# Modulator_and_Front_End.net
KiCad netlist of a schematic drawn in EAGLE
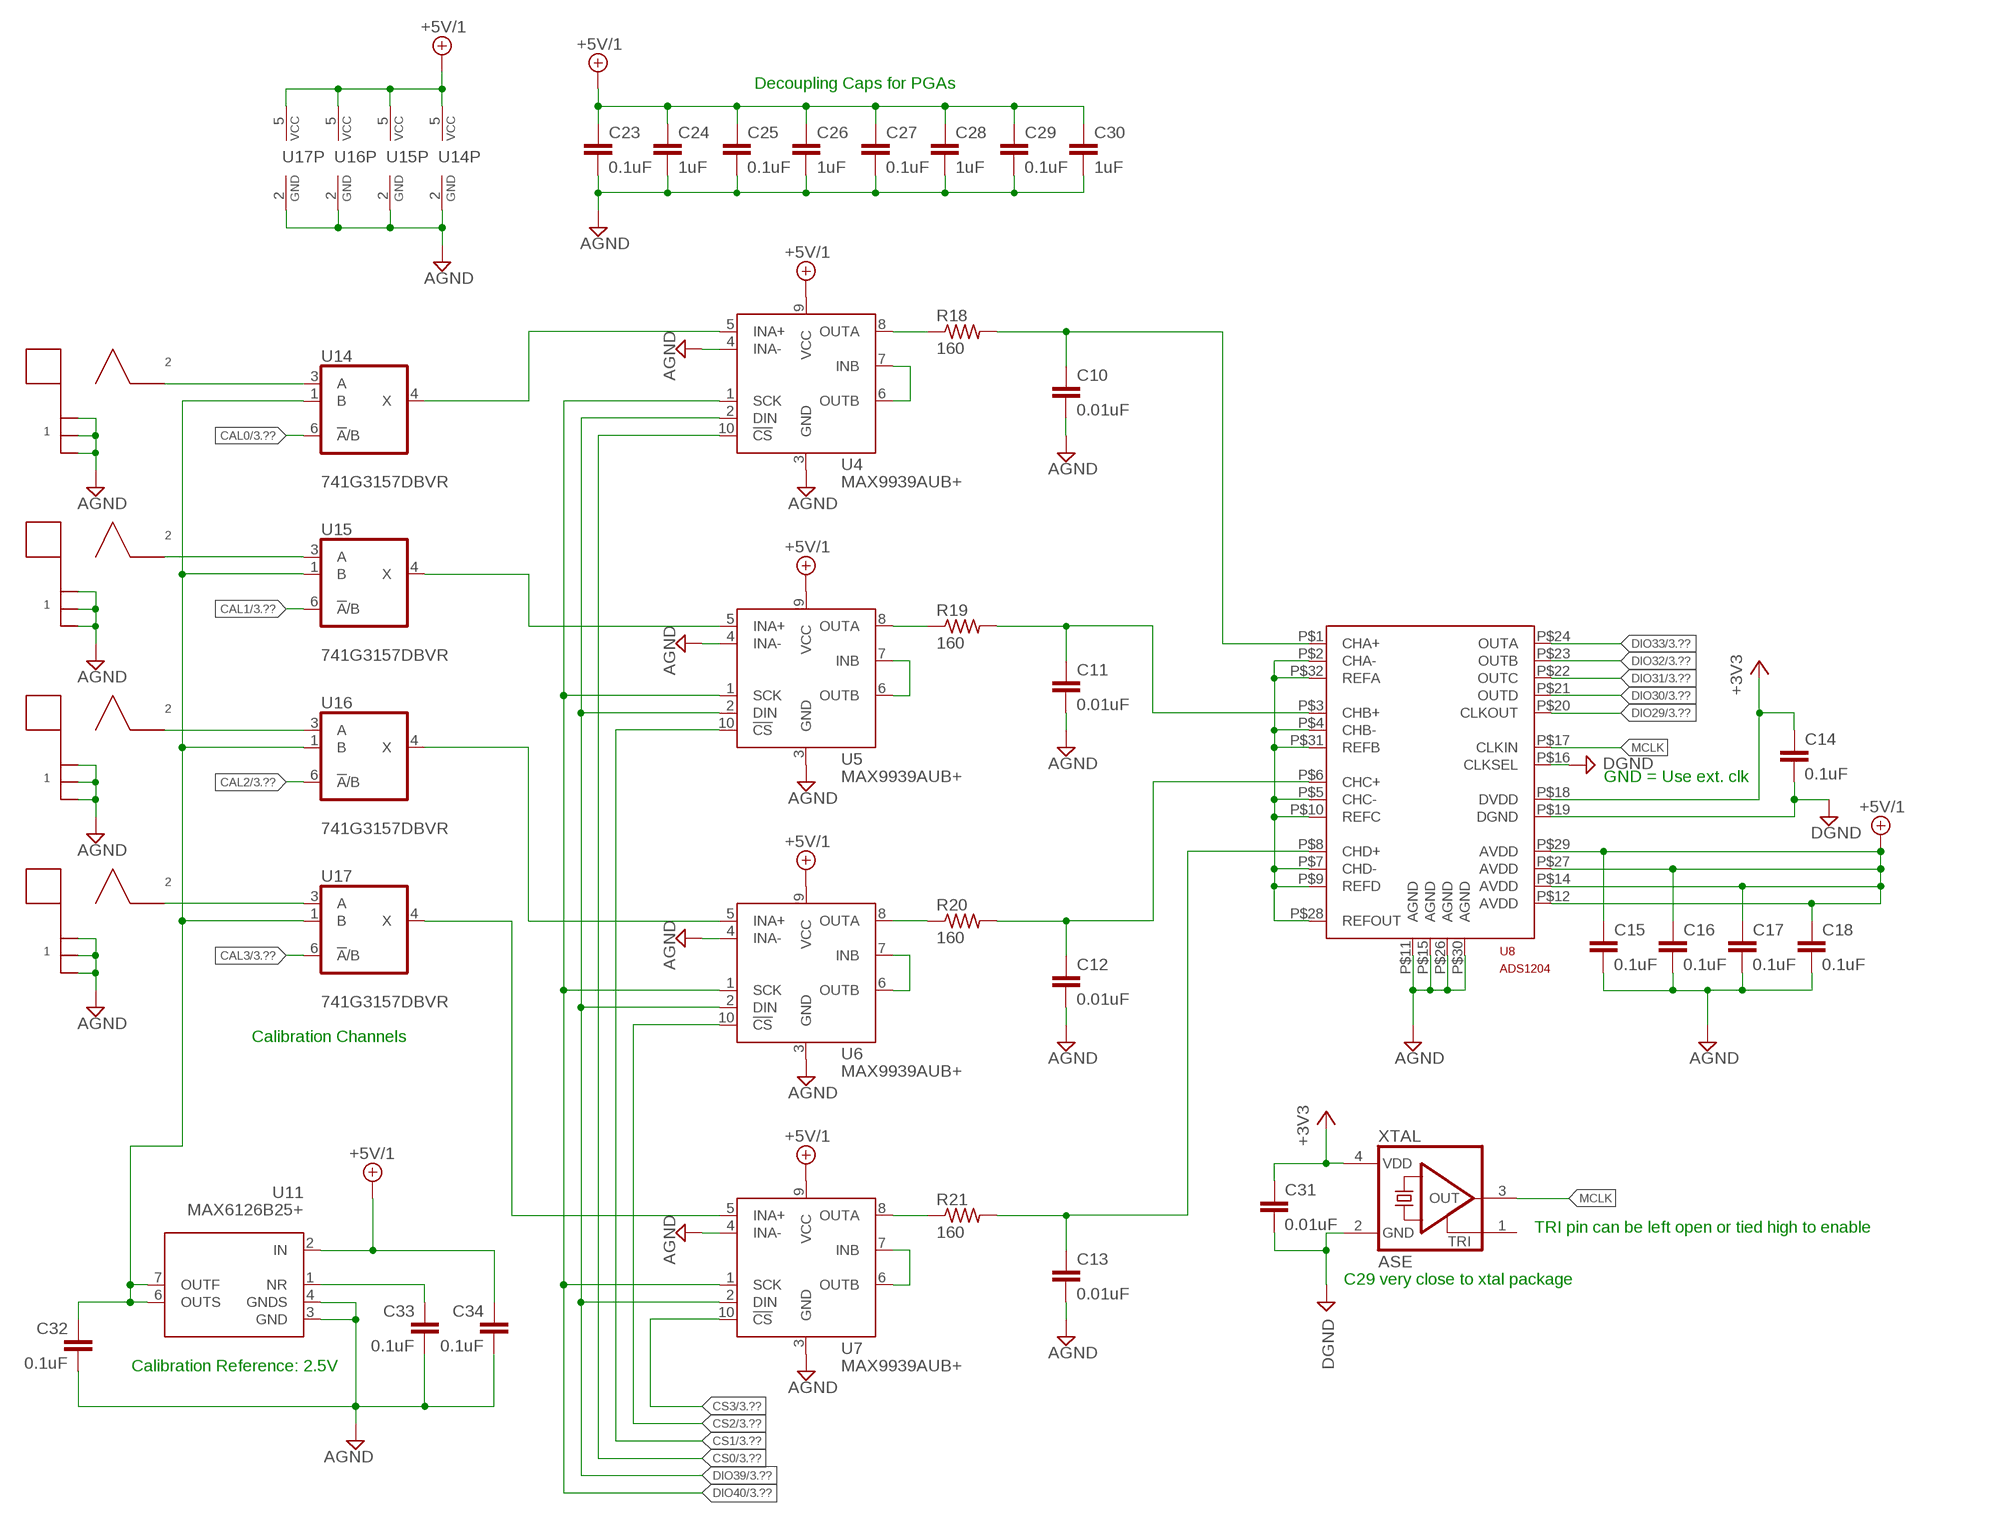
[diagram p0: schematic, sheet 1]
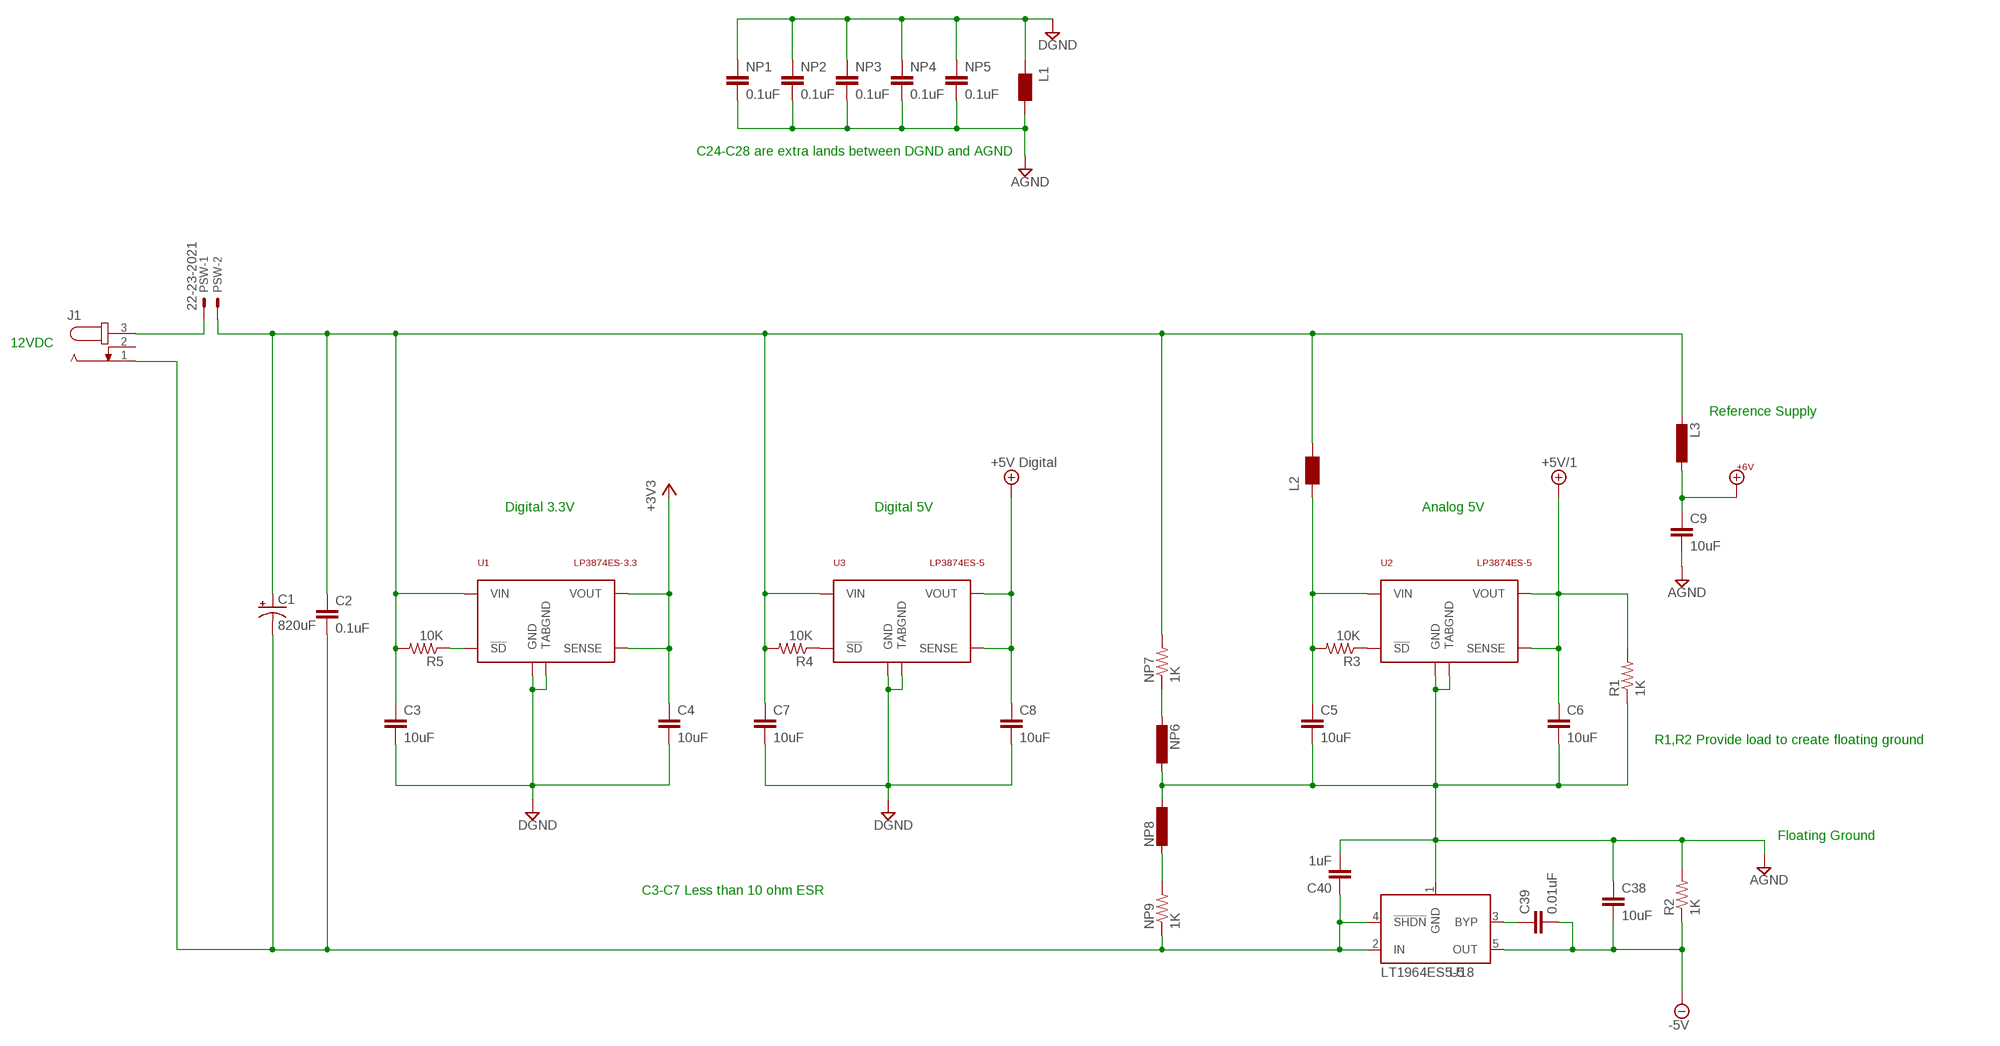
[diagram p1: schematic, sheet 2]
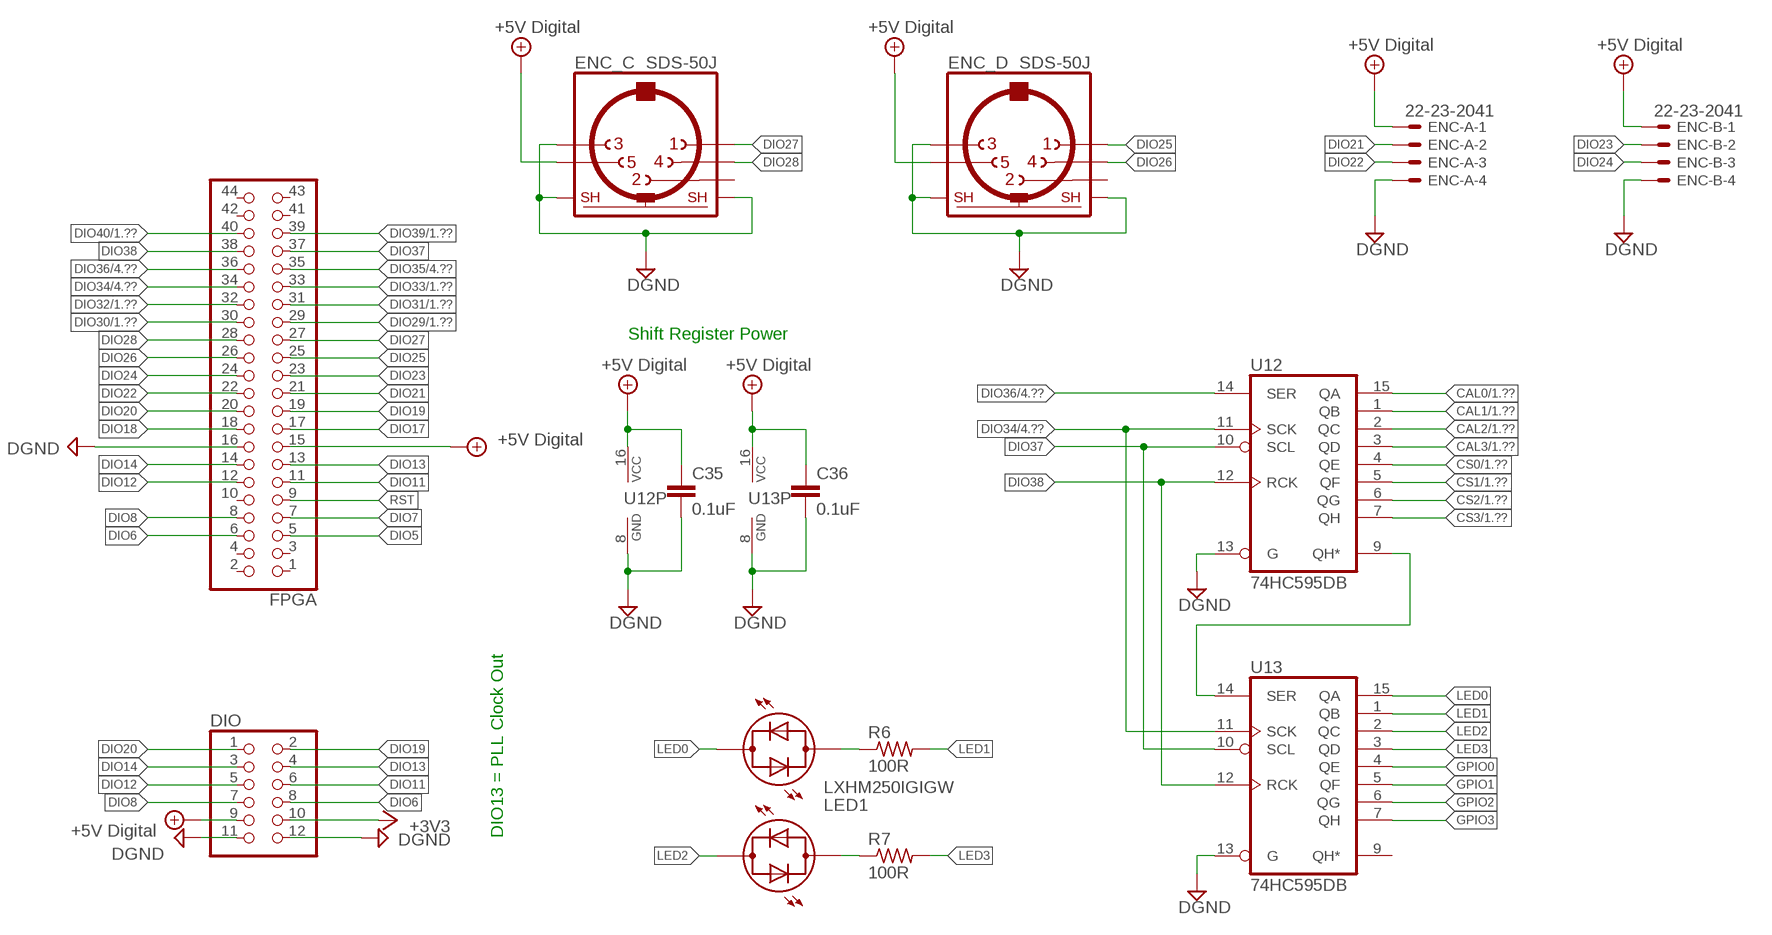
[diagram p2: schematic, sheet 3]
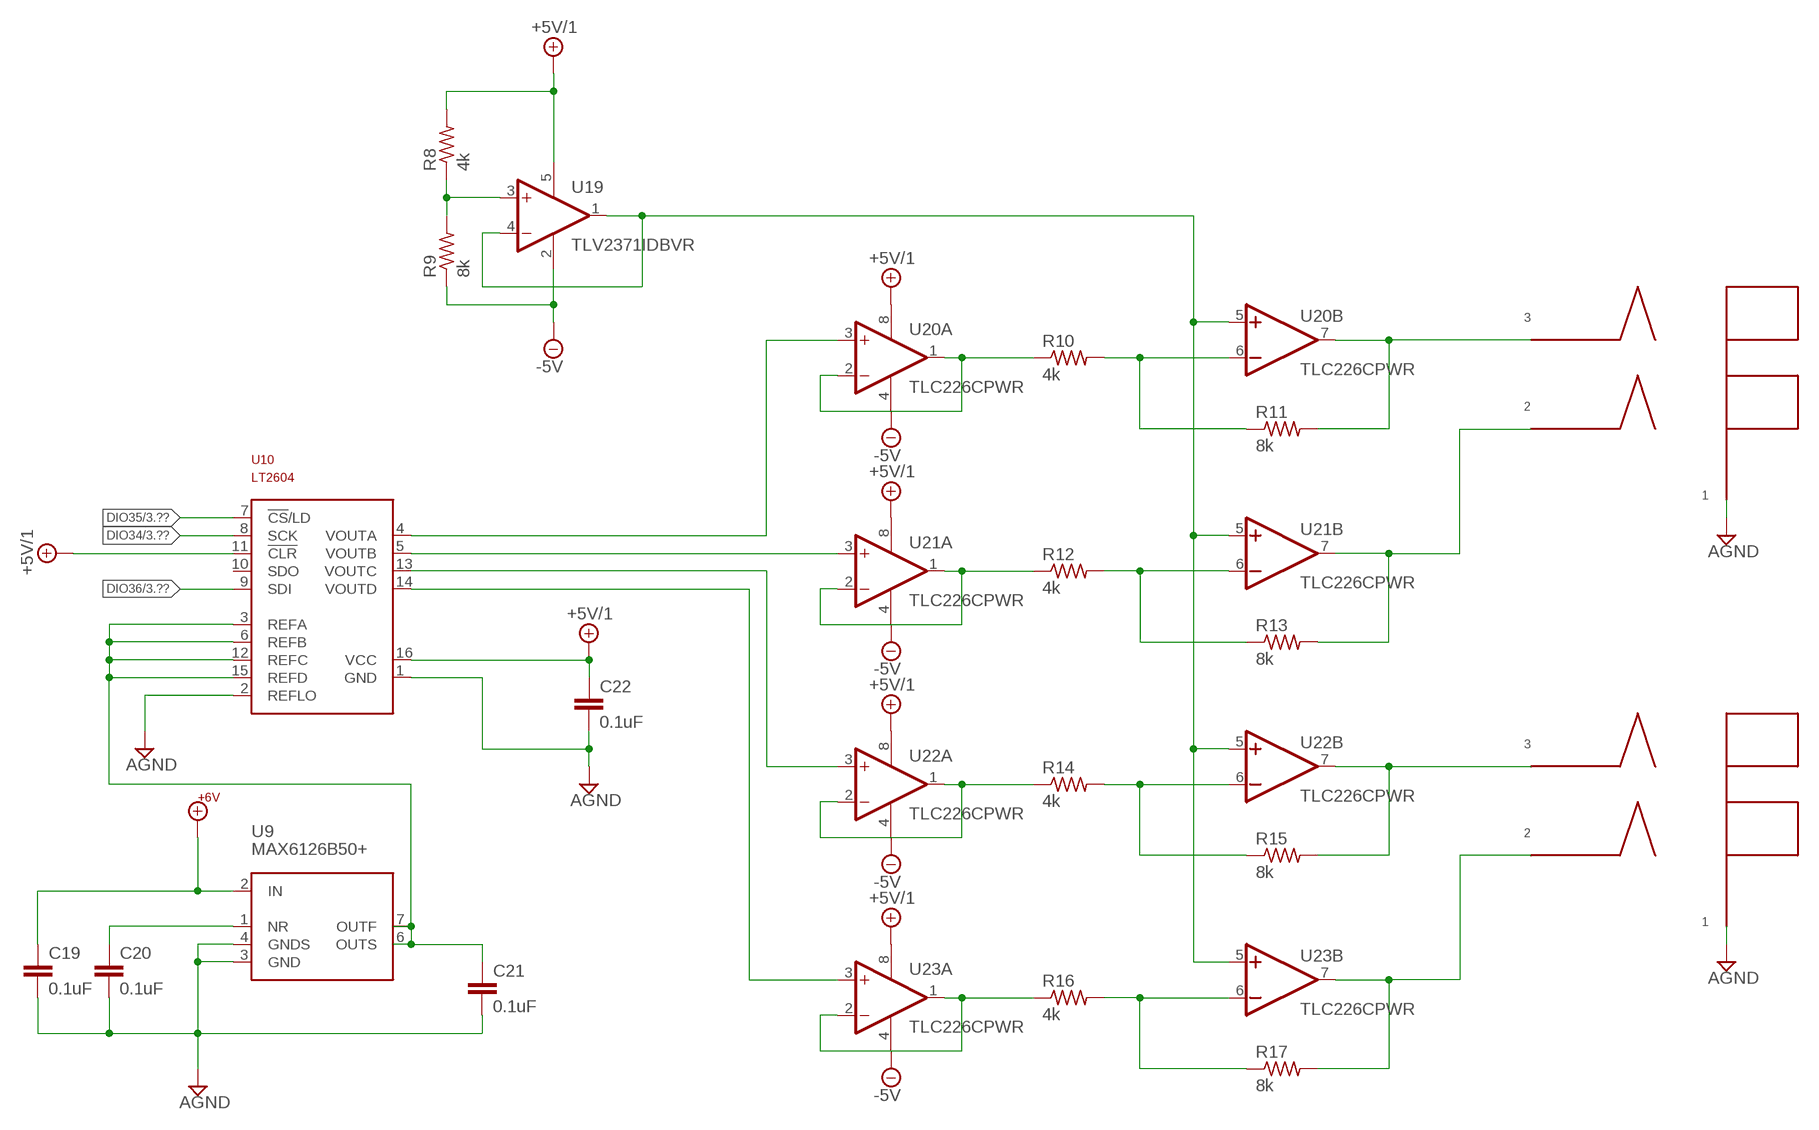
[diagram p3: schematic, sheet 4]

(export (version "E")
  (design (tool "Eeschema 10.0.6"))
  (components
    (comp (ref "C35")
      (value "0.1uF")
      (footprint "eagle-import:C0805")
      (fields (field (name "PARTNO") "LMK212SD104KG-T"))
      (libsource (lib "eagle-import") (part "C-EUC0805"))
    )
    (comp (ref "C36")
      (value "0.1uF")
      (footprint "eagle-import:C0805")
      (fields (field (name "PARTNO") "LMK212SD104KG-T"))
      (libsource (lib "eagle-import") (part "C-EUC0805"))
    )
    (comp (ref "DIO")
      (value "PINHD-2X6")
      (footprint "eagle-import:2X06")
      (fields (field (name "PARTNO") "68602-112HLF"))
      (libsource (lib "eagle-import") (part "PINHD-2X6"))
    )
    (comp (ref "ENC-A")
      (value "22-23-2041")
      (footprint "eagle-import:22-23-2041")
      (fields (field (name "MF") "MOLEX") (field (name "PARTNO") "22-23-2041"))
      (libsource (lib "eagle-import") (part "22-23-2041"))
    )
    (comp (ref "ENC-B")
      (value "22-23-2041")
      (footprint "eagle-import:22-23-2041")
      (fields (field (name "MF") "MOLEX") (field (name "PARTNO") "22-23-2041"))
      (libsource (lib "eagle-import") (part "22-23-2041"))
    )
    (comp (ref "ENC_C")
      (value "SDS-50J")
      (footprint "eagle-import:SDS-50J")
      (libsource (lib "eagle-import") (part "SDS-50J"))
    )
    (comp (ref "ENC_D")
      (value "SDS-50J")
      (footprint "eagle-import:SDS-50J")
      (libsource (lib "eagle-import") (part "SDS-50J"))
    )
    (comp (ref "FPGA")
      (value "PINHD-2X22")
      (footprint "eagle-import:2X22")
      (libsource (lib "eagle-import") (part "PINHD-2X22"))
    )
    (comp (ref "LED1")
      (value "LXHM250IGIGW")
      (footprint "eagle-import:LXHM250IGIGW")
      (fields (field (name "PARTNO") "SSF-LXHM250IGIGW"))
      (libsource (lib "eagle-import") (part "LXHM250IGIGW"))
    )
    (comp (ref "R6")
      (value "100R")
      (footprint "eagle-import:R0805")
      (fields (field (name "PARTNO") "ERJ-6GEYJ101V"))
      (libsource (lib "eagle-import") (part "R-US_R0805"))
    )
    (comp (ref "R7")
      (value "100R")
      (footprint "eagle-import:R0805")
      (fields (field (name "PARTNO") "ERJ-6GEYJ101V"))
      (libsource (lib "eagle-import") (part "R-US_R0805"))
    )
    (comp (ref "U12")
      (value "74HC595DB")
      (footprint "eagle-import:SSOP16")
      (fields (field (name "PARTNO") "\"74HC595DB,112\""))
      (libsource (lib "eagle-import") (part "74595DBHC"))
    )
    (comp (ref "U13")
      (value "74HC595DB")
      (footprint "eagle-import:SSOP16")
      (fields (field (name "PARTNO") "\"74HC595DB,112\""))
      (libsource (lib "eagle-import") (part "74595DBHC"))
    )
    (comp (ref "C19")
      (value "0.1uF")
      (footprint "eagle-import:C0805")
      (fields (field (name "PARTNO") "LMK212SD104KG-T"))
      (libsource (lib "eagle-import") (part "C-EUC0805"))
    )
    (comp (ref "C20")
      (value "0.1uF")
      (footprint "eagle-import:C0805")
      (fields (field (name "PARTNO") "LMK212SD104KG-T"))
      (libsource (lib "eagle-import") (part "C-EUC0805"))
    )
    (comp (ref "C21")
      (value "0.1uF")
      (footprint "eagle-import:C0805")
      (fields (field (name "PARTNO") "LMK212SD104KG-T"))
      (libsource (lib "eagle-import") (part "C-EUC0805"))
    )
    (comp (ref "C22")
      (value "0.1uF")
      (footprint "eagle-import:C0805")
      (fields (field (name "PARTNO") "LMK212SD104KG-T"))
      (libsource (lib "eagle-import") (part "C-EUC0805"))
    )
    (comp (ref "OUTAB")
      (value "RCJ-22XX")
      (footprint "eagle-import:RCJ-22XX")
      (fields (field (name "PARTNO") "RCJ-2221"))
      (libsource (lib "eagle-import") (part "RCJ-22XX"))
    )
    (comp (ref "OUTCD")
      (value "RCJ-22XX")
      (footprint "eagle-import:RCJ-22XX")
      (fields (field (name "PARTNO") "RCJ-2234"))
      (libsource (lib "eagle-import") (part "RCJ-22XX"))
    )
    (comp (ref "R8")
      (value "4k")
      (footprint "eagle-import:R0805")
      (fields (field (name "PARTNO") "ERJ-6ENF5101V"))
      (libsource (lib "eagle-import") (part "R-US_R0805"))
    )
    (comp (ref "R9")
      (value "8k")
      (footprint "eagle-import:R0805")
      (fields (field (name "PARTNO") "ERJ-6ENF1022V"))
      (libsource (lib "eagle-import") (part "R-US_R0805"))
    )
    (comp (ref "R10")
      (value "4k")
      (footprint "eagle-import:R0805")
      (fields (field (name "PARTNO") "ERJ-6ENF5101V"))
      (libsource (lib "eagle-import") (part "R-US_R0805"))
    )
    (comp (ref "R11")
      (value "8k")
      (footprint "eagle-import:R0805")
      (fields (field (name "PARTNO") "ERJ-6ENF1022V"))
      (libsource (lib "eagle-import") (part "R-US_R0805"))
    )
    (comp (ref "R12")
      (value "4k")
      (footprint "eagle-import:R0805")
      (fields (field (name "PARTNO") "ERJ-6ENF5101V"))
      (libsource (lib "eagle-import") (part "R-US_R0805"))
    )
    (comp (ref "R13")
      (value "8k")
      (footprint "eagle-import:R0805")
      (fields (field (name "PARTNO") "ERJ-6ENF1022V"))
      (libsource (lib "eagle-import") (part "R-US_R0805"))
    )
    (comp (ref "R14")
      (value "4k")
      (footprint "eagle-import:R0805")
      (fields (field (name "PARTNO") "ERJ-6ENF5101V"))
      (libsource (lib "eagle-import") (part "R-US_R0805"))
    )
    (comp (ref "R15")
      (value "8k")
      (footprint "eagle-import:R0805")
      (fields (field (name "PARTNO") "ERJ-6ENF1022V"))
      (libsource (lib "eagle-import") (part "R-US_R0805"))
    )
    (comp (ref "R16")
      (value "4k")
      (footprint "eagle-import:R0805")
      (fields (field (name "PARTNO") "ERJ-6ENF5101V"))
      (libsource (lib "eagle-import") (part "R-US_R0805"))
    )
    (comp (ref "R17")
      (value "8k")
      (footprint "eagle-import:R0805")
      (fields (field (name "PARTNO") "ERJ-6ENF1022V"))
      (libsource (lib "eagle-import") (part "R-US_R0805"))
    )
    (comp (ref "U9")
      (value "MAX6126B50+")
      (footprint "eagle-import:UMAX8")
      (libsource (lib "eagle-import") (part "MAX6126B50+"))
    )
    (comp (ref "U10")
      (value "LT2604")
      (footprint "eagle-import:SSOP16")
      (fields (field (name "PARTNO") "LTC2604CGN#PBF"))
      (libsource (lib "eagle-import") (part "LT2604"))
    )
    (comp (ref "U19")
      (value "TLV2371IDBVR")
      (footprint "eagle-import:SOT23-DBV")
      (libsource (lib "eagle-import") (part "TLV2371IDBVR"))
    )
    (comp (ref "U20")
      (value "TLC226CPWR")
      (footprint "eagle-import:TSSOP8")
      (fields (field (name "PARTNO") "TLC2262CPWR"))
      (libsource (lib "eagle-import") (part "TLC226CPWR"))
    )
    (comp (ref "U21")
      (value "TLC226CPWR")
      (footprint "eagle-import:TSSOP8")
      (fields (field (name "PARTNO") "TLC2262CPWR"))
      (libsource (lib "eagle-import") (part "TLC226CPWR"))
    )
    (comp (ref "U22")
      (value "TLC226CPWR")
      (footprint "eagle-import:TSSOP8")
      (fields (field (name "PARTNO") "TLC2262CPWR"))
      (libsource (lib "eagle-import") (part "TLC226CPWR"))
    )
    (comp (ref "U23")
      (value "TLC226CPWR")
      (footprint "eagle-import:TSSOP8")
      (fields (field (name "PARTNO") "TLC2262CPWR"))
      (libsource (lib "eagle-import") (part "TLC226CPWR"))
    )
    (comp (ref "C1")
      (value "820uF")
      (footprint "eagle-import:E5-13")
      (fields (field (name "PARTNO") "EEU-TP1E821"))
      (libsource (lib "eagle-import") (part "CPOL-USE5-13"))
    )
    (comp (ref "C2")
      (value "0.1uF")
      (footprint "eagle-import:C0805")
      (fields (field (name "PARTNO") "LMK212SD104KG-T"))
      (libsource (lib "eagle-import") (part "C-EUC0805"))
    )
    (comp (ref "C3")
      (value "10uF")
      (footprint "eagle-import:C1206")
      (fields (field (name "PARTNO") "F951C106MPAAQ2"))
      (libsource (lib "eagle-import") (part "C-EUC1206"))
    )
    (comp (ref "C4")
      (value "10uF")
      (footprint "eagle-import:C1206")
      (fields (field (name "PARTNO") "F951C106MPAAQ2"))
      (libsource (lib "eagle-import") (part "C-EUC1206"))
    )
    (comp (ref "C5")
      (value "10uF")
      (footprint "eagle-import:C1206")
      (fields (field (name "PARTNO") "F951C106MPAAQ2"))
      (libsource (lib "eagle-import") (part "C-EUC1206"))
    )
    (comp (ref "C6")
      (value "10uF")
      (footprint "eagle-import:C1206")
      (fields (field (name "PARTNO") "F951C106MPAAQ2"))
      (libsource (lib "eagle-import") (part "C-EUC1206"))
    )
    (comp (ref "C7")
      (value "10uF")
      (footprint "eagle-import:C1206")
      (fields (field (name "PARTNO") "F951C106MPAAQ2"))
      (libsource (lib "eagle-import") (part "C-EUC1206"))
    )
    (comp (ref "C8")
      (value "10uF")
      (footprint "eagle-import:C1206")
      (fields (field (name "PARTNO") "F951C106MPAAQ2"))
      (libsource (lib "eagle-import") (part "C-EUC1206"))
    )
    (comp (ref "C9")
      (value "10uF")
      (footprint "eagle-import:C1206")
      (fields (field (name "PARTNO") "F951C106MPAAQ2"))
      (libsource (lib "eagle-import") (part "C-EUC1206"))
    )
    (comp (ref "C38")
      (value "10uF")
      (footprint "eagle-import:C1206")
      (fields (field (name "PARTNO") "F951C106MPAAQ2"))
      (libsource (lib "eagle-import") (part "C-EUC1206"))
    )
    (comp (ref "C39")
      (value "0.01uF")
      (footprint "eagle-import:C1206")
      (fields (field (name "PARTNO") "0805YA103JAT2A"))
      (libsource (lib "eagle-import") (part "C-EUC1206"))
    )
    (comp (ref "C40")
      (value "1uF")
      (footprint "eagle-import:C1206")
      (fields (field (name "PARTNO") "C2012X7R1A105K"))
      (libsource (lib "eagle-import") (part "C-EUC1206"))
    )
    (comp (ref "J1")
      (value "JACK-PLUG1")
      (footprint "eagle-import:SPC4078")
      (fields (field (name "PARTNO") "PJ-102B"))
      (libsource (lib "eagle-import") (part "JACK-PLUG1"))
    )
    (comp (ref "L1")
      (value "WE-CBF_0603")
      (footprint "eagle-import:0603")
      (fields (field (name "PARTNO") "MPZ1608S101A"))
      (libsource (lib "eagle-import") (part "WE-CBF_0603"))
    )
    (comp (ref "L2")
      (value "WE-CBF_0603")
      (footprint "eagle-import:0603")
      (fields (field (name "PARTNO") "MPZ1608S101A"))
      (libsource (lib "eagle-import") (part "WE-CBF_0603"))
    )
    (comp (ref "L3")
      (value "L-EUL1812")
      (footprint "eagle-import:L1812")
      (fields (field (name "PARTNO") "NLC453232T-100K-PF"))
      (libsource (lib "eagle-import") (part "L-EUL1812"))
    )
    (comp (ref "NP1")
      (value "0.1uF")
      (footprint "eagle-import:C0805")
      (libsource (lib "eagle-import") (part "C-EUC0805"))
    )
    (comp (ref "NP2")
      (value "0.1uF")
      (footprint "eagle-import:C0805")
      (libsource (lib "eagle-import") (part "C-EUC0805"))
    )
    (comp (ref "NP3")
      (value "0.1uF")
      (footprint "eagle-import:C0805")
      (libsource (lib "eagle-import") (part "C-EUC0805"))
    )
    (comp (ref "NP4")
      (value "0.1uF")
      (footprint "eagle-import:C0805")
      (libsource (lib "eagle-import") (part "C-EUC0805"))
    )
    (comp (ref "NP5")
      (value "0.1uF")
      (footprint "eagle-import:C0805")
      (libsource (lib "eagle-import") (part "C-EUC0805"))
    )
    (comp (ref "NP6")
      (value "L-EUL1812")
      (footprint "eagle-import:L1812")
      (libsource (lib "eagle-import") (part "L-EUL1812"))
    )
    (comp (ref "NP7")
      (value "1K")
      (footprint "eagle-import:M0805")
      (libsource (lib "eagle-import") (part "R-US_M0805"))
    )
    (comp (ref "NP8")
      (value "L-EUL1812")
      (footprint "eagle-import:L1812")
      (libsource (lib "eagle-import") (part "L-EUL1812"))
    )
    (comp (ref "NP9")
      (value "1K")
      (footprint "eagle-import:M0805")
      (libsource (lib "eagle-import") (part "R-US_M0805"))
    )
    (comp (ref "PSW")
      (value "22-23-2021")
      (footprint "eagle-import:22-23-2021")
      (fields (field (name "MF") "MOLEX") (field (name "PARTNO") "22-23-2021"))
      (libsource (lib "eagle-import") (part "22-23-2021"))
    )
    (comp (ref "R1")
      (value "1K")
      (footprint "eagle-import:M0805")
      (fields (field (name "PARTNO") "ERJ-6GEYJ102V"))
      (libsource (lib "eagle-import") (part "R-US_M0805"))
    )
    (comp (ref "R2")
      (value "1K")
      (footprint "eagle-import:M0805")
      (fields (field (name "PARTNO") "ERJ-6GEYJ102V"))
      (libsource (lib "eagle-import") (part "R-US_M0805"))
    )
    (comp (ref "R3")
      (value "10K")
      (footprint "eagle-import:M0805")
      (fields (field (name "PARTNO") "ERJ-6GEYJ103V"))
      (libsource (lib "eagle-import") (part "R-US_M0805"))
    )
    (comp (ref "R4")
      (value "10K")
      (footprint "eagle-import:M0805")
      (fields (field (name "PARTNO") "ERJ-6GEYJ103V"))
      (libsource (lib "eagle-import") (part "R-US_M0805"))
    )
    (comp (ref "R5")
      (value "10K")
      (footprint "eagle-import:M0805")
      (fields (field (name "PARTNO") "ERJ-6GEYJ103V"))
      (libsource (lib "eagle-import") (part "R-US_M0805"))
    )
    (comp (ref "U1")
      (value "LP3874ES-3.3")
      (footprint "eagle-import:TO263-5")
      (fields (field (name "PARTNO") "LP3872ES-3.3/NOPB"))
      (libsource (lib "eagle-import") (part "LP3874ES?-3.3"))
    )
    (comp (ref "U2")
      (value "LP3874ES-5")
      (footprint "eagle-import:TO263-5")
      (fields (field (name "PARTNO") "LP3872ES-5.0/NOPB"))
      (libsource (lib "eagle-import") (part "LP3874ES?-5"))
    )
    (comp (ref "U3")
      (value "LP3874ES-5")
      (footprint "eagle-import:TO263-5")
      (fields (field (name "PARTNO") "LP3872ES-5.0/NOPB"))
      (libsource (lib "eagle-import") (part "LP3874ES?-5"))
    )
    (comp (ref "U18")
      (value "LT1964ES5-5")
      (footprint "eagle-import:SOT23-5")
      (fields (field (name "PARTNO") "LT1964ES5-5#TRMPBF"))
      (libsource (lib "eagle-import") (part "LT1964ES5-5"))
    )
    (comp (ref "C10")
      (value "0.01uF")
      (footprint "eagle-import:C0805")
      (fields (field (name "PARTNO") "0805YA103JAT2A"))
      (libsource (lib "eagle-import") (part "C-EUC0805"))
    )
    (comp (ref "C11")
      (value "0.01uF")
      (footprint "eagle-import:C0805")
      (fields (field (name "PARTNO") "0805YA103JAT2A"))
      (libsource (lib "eagle-import") (part "C-EUC0805"))
    )
    (comp (ref "C12")
      (value "0.01uF")
      (footprint "eagle-import:C0805")
      (fields (field (name "PARTNO") "0805YA103JAT2A"))
      (libsource (lib "eagle-import") (part "C-EUC0805"))
    )
    (comp (ref "C13")
      (value "0.01uF")
      (footprint "eagle-import:C0805")
      (fields (field (name "PARTNO") "0805YA103JAT2A"))
      (libsource (lib "eagle-import") (part "C-EUC0805"))
    )
    (comp (ref "C14")
      (value "0.1uF")
      (footprint "eagle-import:C0805")
      (fields (field (name "PARTNO") "LMK212SD104KG-T"))
      (libsource (lib "eagle-import") (part "C-EUC0805"))
    )
    (comp (ref "C15")
      (value "0.1uF")
      (footprint "eagle-import:C0805")
      (fields (field (name "PARTNO") "LMK212SD104KG-T"))
      (libsource (lib "eagle-import") (part "C-EUC0805"))
    )
    (comp (ref "C16")
      (value "0.1uF")
      (footprint "eagle-import:C0805")
      (fields (field (name "PARTNO") "LMK212SD104KG-T"))
      (libsource (lib "eagle-import") (part "C-EUC0805"))
    )
    (comp (ref "C17")
      (value "0.1uF")
      (footprint "eagle-import:C0805")
      (fields (field (name "PARTNO") "LMK212SD104KG-T"))
      (libsource (lib "eagle-import") (part "C-EUC0805"))
    )
    (comp (ref "C18")
      (value "0.1uF")
      (footprint "eagle-import:C0805")
      (fields (field (name "PARTNO") "LMK212SD104KG-T"))
      (libsource (lib "eagle-import") (part "C-EUC0805"))
    )
    (comp (ref "C23")
      (value "0.1uF")
      (footprint "eagle-import:C0805")
      (fields (field (name "PARTNO") "LMK212SD104KG-T"))
      (libsource (lib "eagle-import") (part "C-EUC0805"))
    )
    (comp (ref "C24")
      (value "1uF")
      (footprint "eagle-import:C0805")
      (fields (field (name "PARTNO") "C2012X7R1A105K"))
      (libsource (lib "eagle-import") (part "C-EUC0805"))
    )
    (comp (ref "C25")
      (value "0.1uF")
      (footprint "eagle-import:C0805")
      (fields (field (name "PARTNO") "LMK212SD104KG-T"))
      (libsource (lib "eagle-import") (part "C-EUC0805"))
    )
    (comp (ref "C26")
      (value "1uF")
      (footprint "eagle-import:C0805")
      (fields (field (name "PARTNO") "C2012X7R1A105K"))
      (libsource (lib "eagle-import") (part "C-EUC0805"))
    )
    (comp (ref "C27")
      (value "0.1uF")
      (footprint "eagle-import:C0805")
      (fields (field (name "PARTNO") "LMK212SD104KG-T"))
      (libsource (lib "eagle-import") (part "C-EUC0805"))
    )
    (comp (ref "C28")
      (value "1uF")
      (footprint "eagle-import:C0805")
      (fields (field (name "PARTNO") "C2012X7R1A105K"))
      (libsource (lib "eagle-import") (part "C-EUC0805"))
    )
    (comp (ref "C29")
      (value "0.1uF")
      (footprint "eagle-import:C0805")
      (fields (field (name "PARTNO") "LMK212SD104KG-T"))
      (libsource (lib "eagle-import") (part "C-EUC0805"))
    )
    (comp (ref "C30")
      (value "1uF")
      (footprint "eagle-import:C0805")
      (fields (field (name "PARTNO") "C2012X7R1A105K"))
      (libsource (lib "eagle-import") (part "C-EUC0805"))
    )
    (comp (ref "C31")
      (value "0.01uF")
      (footprint "eagle-import:C0805")
      (fields (field (name "PARTNO") "0805YA103JAT2A"))
      (libsource (lib "eagle-import") (part "C-EUC0805"))
    )
    (comp (ref "C32")
      (value "0.1uF")
      (footprint "eagle-import:C0805")
      (fields (field (name "PARTNO") "LMK212SD104KG-T"))
      (libsource (lib "eagle-import") (part "C-EUC0805"))
    )
    (comp (ref "C33")
      (value "0.1uF")
      (footprint "eagle-import:C0805")
      (fields (field (name "PARTNO") "LMK212SD104KG-T"))
      (libsource (lib "eagle-import") (part "C-EUC0805"))
    )
    (comp (ref "C34")
      (value "0.1uF")
      (footprint "eagle-import:C0805")
      (fields (field (name "PARTNO") "LMK212SD104KG-T"))
      (libsource (lib "eagle-import") (part "C-EUC0805"))
    )
    (comp (ref "INA")
      (value "RCJ-01X")
      (footprint "eagle-import:RCJ-01X")
      (fields (field (name "PARTNO") "RCJ-012"))
      (libsource (lib "eagle-import") (part "RCJ-01X"))
    )
    (comp (ref "INB")
      (value "RCJ-01X")
      (footprint "eagle-import:RCJ-01X")
      (fields (field (name "PARTNO") "RCJ-011"))
      (libsource (lib "eagle-import") (part "RCJ-01X"))
    )
    (comp (ref "INC")
      (value "RCJ-01X")
      (footprint "eagle-import:RCJ-01X")
      (fields (field (name "PARTNO") "RCJ-013"))
      (libsource (lib "eagle-import") (part "RCJ-01X"))
    )
    (comp (ref "IND")
      (value "RCJ-01X")
      (footprint "eagle-import:RCJ-01X")
      (fields (field (name "PARTNO") "RCJ-014"))
      (libsource (lib "eagle-import") (part "RCJ-01X"))
    )
    (comp (ref "R18")
      (value "160")
      (footprint "eagle-import:M0805")
      (fields (field (name "PARTNO") "ERJ-6ENF1600V"))
      (libsource (lib "eagle-import") (part "R-US_M0805"))
    )
    (comp (ref "R19")
      (value "160")
      (footprint "eagle-import:M0805")
      (fields (field (name "PARTNO") "ERJ-6ENF1600V"))
      (libsource (lib "eagle-import") (part "R-US_M0805"))
    )
    (comp (ref "R20")
      (value "160")
      (footprint "eagle-import:M0805")
      (fields (field (name "PARTNO") "ERJ-6ENF1600V"))
      (libsource (lib "eagle-import") (part "R-US_M0805"))
    )
    (comp (ref "R21")
      (value "160")
      (footprint "eagle-import:M0805")
      (fields (field (name "PARTNO") "ERJ-6ENF1600V"))
      (libsource (lib "eagle-import") (part "R-US_M0805"))
    )
    (comp (ref "U4")
      (value "MAX9939AUB+")
      (footprint "eagle-import:UMAX10")
      (libsource (lib "eagle-import") (part "MAX9939AUB+"))
    )
    (comp (ref "U5")
      (value "MAX9939AUB+")
      (footprint "eagle-import:UMAX10")
      (libsource (lib "eagle-import") (part "MAX9939AUB+"))
    )
    (comp (ref "U6")
      (value "MAX9939AUB+")
      (footprint "eagle-import:UMAX10")
      (libsource (lib "eagle-import") (part "MAX9939AUB+"))
    )
    (comp (ref "U7")
      (value "MAX9939AUB+")
      (footprint "eagle-import:UMAX10")
      (libsource (lib "eagle-import") (part "MAX9939AUB+"))
    )
    (comp (ref "U8")
      (value "ADS1204")
      (footprint "eagle-import:QFN-32")
      (fields (field (name "PARTNO") "ADS1204IRHBT"))
      (libsource (lib "eagle-import") (part "ADS1204"))
    )
    (comp (ref "U11")
      (value "MAX6126B25+")
      (footprint "eagle-import:UMAX8")
      (libsource (lib "eagle-import") (part "MAX6126B25+"))
    )
    (comp (ref "U14")
      (value "741G3157DBVR")
      (footprint "eagle-import:DBV_R-PDSO-G6")
      (fields (field (name "PARTNO") "\"74LVC1G3157GW,125\""))
      (libsource (lib "eagle-import") (part "741G3157DBVR"))
    )
    (comp (ref "U15")
      (value "741G3157DBVR")
      (footprint "eagle-import:DBV_R-PDSO-G6")
      (fields (field (name "PARTNO") "\"74LVC1G3157GW,125\""))
      (libsource (lib "eagle-import") (part "741G3157DBVR"))
    )
    (comp (ref "U16")
      (value "741G3157DBVR")
      (footprint "eagle-import:DBV_R-PDSO-G6")
      (fields (field (name "PARTNO") "\"74LVC1G3157GW,125\""))
      (libsource (lib "eagle-import") (part "741G3157DBVR"))
    )
    (comp (ref "U17")
      (value "741G3157DBVR")
      (footprint "eagle-import:DBV_R-PDSO-G6")
      (fields (field (name "PARTNO") "\"74LVC1G3157GW,125\""))
      (libsource (lib "eagle-import") (part "741G3157DBVR"))
    )
    (comp (ref "XTAL")
      (value "ASE")
      (footprint "eagle-import:ASE")
      (fields (field (name "PARTNO") "CB3LV-3C-20M4800"))
      (libsource (lib "eagle-import") (part "ASE"))
    )
  )
  (nets
    (net (code "1") (name "+3V3") (class "Default")
      (node (ref "C14") (pin "1") (pinfunction "1_1") (pintype "passive"))
      (node (ref "C31") (pin "1") (pinfunction "1_1") (pintype "passive"))
      (node (ref "C4") (pin "1") (pinfunction "1_1") (pintype "passive"))
      (node (ref "DIO") (pin "10") (pinfunction "10_10") (pintype "passive"))
      (node (ref "U1") (pin "4") (pinfunction "VOUT_4") (pintype "passive"))
      (node (ref "U1") (pin "5") (pinfunction "SENSE_5") (pintype "input"))
      (node (ref "U8") (pin "P$18") (pinfunction "DVDD_P$18") (pintype "bidirectional"))
      (node (ref "XTAL") (pin "4") (pinfunction "VDD_4") (pintype "power_in"))
    )
    (net (code "2") (name "+5V{slash}1") (class "Default")
      (node (ref "C15") (pin "1") (pinfunction "1_1") (pintype "passive"))
      (node (ref "C16") (pin "1") (pinfunction "1_1") (pintype "passive"))
      (node (ref "C17") (pin "1") (pinfunction "1_1") (pintype "passive"))
      (node (ref "C18") (pin "1") (pinfunction "1_1") (pintype "passive"))
      (node (ref "C22") (pin "1") (pinfunction "1_1") (pintype "passive"))
      (node (ref "C23") (pin "1") (pinfunction "1_1") (pintype "passive"))
      (node (ref "C24") (pin "1") (pinfunction "1_1") (pintype "passive"))
      (node (ref "C25") (pin "1") (pinfunction "1_1") (pintype "passive"))
      (node (ref "C26") (pin "1") (pinfunction "1_1") (pintype "passive"))
      (node (ref "C27") (pin "1") (pinfunction "1_1") (pintype "passive"))
      (node (ref "C28") (pin "1") (pinfunction "1_1") (pintype "passive"))
      (node (ref "C29") (pin "1") (pinfunction "1_1") (pintype "passive"))
      (node (ref "C30") (pin "1") (pinfunction "1_1") (pintype "passive"))
      (node (ref "C34") (pin "1") (pinfunction "1_1") (pintype "passive"))
      (node (ref "C6") (pin "1") (pinfunction "1_1") (pintype "passive"))
      (node (ref "R1") (pin "2") (pinfunction "2_2") (pintype "passive"))
      (node (ref "R8") (pin "2") (pinfunction "2_2") (pintype "passive"))
      (node (ref "U10") (pin "11") (pinfunction "~{CLR}_11") (pintype "bidirectional"))
      (node (ref "U10") (pin "16") (pinfunction "VCC_16") (pintype "bidirectional"))
      (node (ref "U11") (pin "2") (pinfunction "IN_2") (pintype "bidirectional"))
      (node (ref "U14") (pin "5") (pinfunction "VCC_5") (pintype "power_in"))
      (node (ref "U15") (pin "5") (pinfunction "VCC_5") (pintype "power_in"))
      (node (ref "U16") (pin "5") (pinfunction "VCC_5") (pintype "power_in"))
      (node (ref "U17") (pin "5") (pinfunction "VCC_5") (pintype "power_in"))
      (node (ref "U19") (pin "5") (pinfunction "V+_5") (pintype "power_in"))
      (node (ref "U2") (pin "4") (pinfunction "VOUT_4") (pintype "passive"))
      (node (ref "U2") (pin "5") (pinfunction "SENSE_5") (pintype "input"))
      (node (ref "U20") (pin "8") (pinfunction "V+_8") (pintype "power_in"))
      (node (ref "U21") (pin "8") (pinfunction "V+_8") (pintype "power_in"))
      (node (ref "U22") (pin "8") (pinfunction "V+_8") (pintype "power_in"))
      (node (ref "U23") (pin "8") (pinfunction "V+_8") (pintype "power_in"))
      (node (ref "U4") (pin "9") (pinfunction "VCC_9") (pintype "bidirectional"))
      (node (ref "U5") (pin "9") (pinfunction "VCC_9") (pintype "bidirectional"))
      (node (ref "U6") (pin "9") (pinfunction "VCC_9") (pintype "bidirectional"))
      (node (ref "U7") (pin "9") (pinfunction "VCC_9") (pintype "bidirectional"))
      (node (ref "U8") (pin "P$12") (pinfunction "AVDD_P$12") (pintype "bidirectional"))
      (node (ref "U8") (pin "P$14") (pinfunction "AVDD_P$14") (pintype "bidirectional"))
      (node (ref "U8") (pin "P$27") (pinfunction "AVDD_P$27") (pintype "bidirectional"))
      (node (ref "U8") (pin "P$29") (pinfunction "AVDD_P$29") (pintype "bidirectional"))
    )
    (net (code "3") (name "+5V{slash}2") (class "Default")
      (node (ref "C35") (pin "1") (pinfunction "1_1") (pintype "passive"))
      (node (ref "C36") (pin "1") (pinfunction "1_1") (pintype "passive"))
      (node (ref "C8") (pin "1") (pinfunction "1_1") (pintype "passive"))
      (node (ref "DIO") (pin "9") (pinfunction "9_9") (pintype "passive"))
      (node (ref "ENC-A") (pin "1") (pinfunction "S_1") (pintype "passive"))
      (node (ref "ENC-B") (pin "1") (pinfunction "S_1") (pintype "passive"))
      (node (ref "ENC_C") (pin "5") (pinfunction "5_5") (pintype "passive"))
      (node (ref "ENC_D") (pin "5") (pinfunction "5_5") (pintype "passive"))
      (node (ref "FPGA") (pin "15") (pinfunction "15_15") (pintype "passive"))
      (node (ref "U12") (pin "16") (pinfunction "VCC_16") (pintype "power_in"))
      (node (ref "U13") (pin "16") (pinfunction "VCC_16") (pintype "power_in"))
      (node (ref "U3") (pin "4") (pinfunction "VOUT_4") (pintype "passive"))
      (node (ref "U3") (pin "5") (pinfunction "SENSE_5") (pintype "input"))
    )
    (net (code "4") (name "+6V") (class "Default")
      (node (ref "C19") (pin "1") (pinfunction "1_1") (pintype "passive"))
      (node (ref "C9") (pin "1") (pinfunction "1_1") (pintype "passive"))
      (node (ref "L3") (pin "1") (pinfunction "1_1") (pintype "passive"))
      (node (ref "U9") (pin "2") (pinfunction "IN_2") (pintype "bidirectional"))
    )
    (net (code "5") (name "-5V") (class "Default")
      (node (ref "C38") (pin "2") (pinfunction "2_2") (pintype "passive"))
      (node (ref "C39") (pin "2") (pinfunction "2_2") (pintype "passive"))
      (node (ref "R2") (pin "1") (pinfunction "1_1") (pintype "passive"))
      (node (ref "R9") (pin "1") (pinfunction "1_1") (pintype "passive"))
      (node (ref "U18") (pin "5") (pinfunction "OUT_5") (pintype "bidirectional"))
      (node (ref "U19") (pin "2") (pinfunction "V-_2") (pintype "power_in"))
      (node (ref "U20") (pin "4") (pinfunction "V-_4") (pintype "power_in"))
      (node (ref "U21") (pin "4") (pinfunction "V-_4") (pintype "power_in"))
      (node (ref "U22") (pin "4") (pinfunction "V-_4") (pintype "power_in"))
      (node (ref "U23") (pin "4") (pinfunction "V-_4") (pintype "power_in"))
    )
    (net (code "6") (name "AGND") (class "Default")
      (node (ref "C10") (pin "2") (pinfunction "2_2") (pintype "passive"))
      (node (ref "C11") (pin "2") (pinfunction "2_2") (pintype "passive"))
      (node (ref "C12") (pin "2") (pinfunction "2_2") (pintype "passive"))
      (node (ref "C13") (pin "2") (pinfunction "2_2") (pintype "passive"))
      (node (ref "C15") (pin "2") (pinfunction "2_2") (pintype "passive"))
      (node (ref "C16") (pin "2") (pinfunction "2_2") (pintype "passive"))
      (node (ref "C17") (pin "2") (pinfunction "2_2") (pintype "passive"))
      (node (ref "C18") (pin "2") (pinfunction "2_2") (pintype "passive"))
      (node (ref "C19") (pin "2") (pinfunction "2_2") (pintype "passive"))
      (node (ref "C20") (pin "2") (pinfunction "2_2") (pintype "passive"))
      (node (ref "C21") (pin "2") (pinfunction "2_2") (pintype "passive"))
      (node (ref "C22") (pin "2") (pinfunction "2_2") (pintype "passive"))
      (node (ref "C23") (pin "2") (pinfunction "2_2") (pintype "passive"))
      (node (ref "C24") (pin "2") (pinfunction "2_2") (pintype "passive"))
      (node (ref "C25") (pin "2") (pinfunction "2_2") (pintype "passive"))
      (node (ref "C26") (pin "2") (pinfunction "2_2") (pintype "passive"))
      (node (ref "C27") (pin "2") (pinfunction "2_2") (pintype "passive"))
      (node (ref "C28") (pin "2") (pinfunction "2_2") (pintype "passive"))
      (node (ref "C29") (pin "2") (pinfunction "2_2") (pintype "passive"))
      (node (ref "C30") (pin "2") (pinfunction "2_2") (pintype "passive"))
      (node (ref "C32") (pin "2") (pinfunction "2_2") (pintype "passive"))
      (node (ref "C33") (pin "2") (pinfunction "2_2") (pintype "passive"))
      (node (ref "C34") (pin "2") (pinfunction "2_2") (pintype "passive"))
      (node (ref "C38") (pin "1") (pinfunction "1_1") (pintype "passive"))
      (node (ref "C40") (pin "2") (pinfunction "2_2") (pintype "passive"))
      (node (ref "C5") (pin "2") (pinfunction "2_2") (pintype "passive"))
      (node (ref "C6") (pin "2") (pinfunction "2_2") (pintype "passive"))
      (node (ref "C9") (pin "2") (pinfunction "2_2") (pintype "passive"))
      (node (ref "INA") (pin "1@1") (pinfunction "1_1@1") (pintype "passive"))
      (node (ref "INA") (pin "1@2") (pinfunction "1_1@2") (pintype "passive"))
      (node (ref "INA") (pin "1@3") (pinfunction "1_1@3") (pintype "passive"))
      (node (ref "INB") (pin "1@1") (pinfunction "1_1@1") (pintype "passive"))
      (node (ref "INB") (pin "1@2") (pinfunction "1_1@2") (pintype "passive"))
      (node (ref "INB") (pin "1@3") (pinfunction "1_1@3") (pintype "passive"))
      (node (ref "INC") (pin "1@1") (pinfunction "1_1@1") (pintype "passive"))
      (node (ref "INC") (pin "1@2") (pinfunction "1_1@2") (pintype "passive"))
      (node (ref "INC") (pin "1@3") (pinfunction "1_1@3") (pintype "passive"))
      (node (ref "IND") (pin "1@1") (pinfunction "1_1@1") (pintype "passive"))
      (node (ref "IND") (pin "1@2") (pinfunction "1_1@2") (pintype "passive"))
      (node (ref "IND") (pin "1@3") (pinfunction "1_1@3") (pintype "passive"))
      (node (ref "L1") (pin "2") (pinfunction "2_2") (pintype "passive"))
      (node (ref "NP1") (pin "2") (pinfunction "2_2") (pintype "passive"))
      (node (ref "NP2") (pin "2") (pinfunction "2_2") (pintype "passive"))
      (node (ref "NP3") (pin "2") (pinfunction "2_2") (pintype "passive"))
      (node (ref "NP4") (pin "2") (pinfunction "2_2") (pintype "passive"))
      (node (ref "NP5") (pin "2") (pinfunction "2_2") (pintype "passive"))
      (node (ref "NP6") (pin "1") (pinfunction "1_1") (pintype "passive"))
      (node (ref "NP8") (pin "1") (pinfunction "1_1") (pintype "passive"))
      (node (ref "OUTAB") (pin "1") (pinfunction "1_1") (pintype "passive"))
      (node (ref "OUTCD") (pin "1") (pinfunction "1_1") (pintype "passive"))
      (node (ref "R1") (pin "1") (pinfunction "1_1") (pintype "passive"))
      (node (ref "R2") (pin "2") (pinfunction "2_2") (pintype "passive"))
      (node (ref "U10") (pin "1") (pinfunction "GND_1") (pintype "bidirectional"))
      (node (ref "U10") (pin "2") (pinfunction "REFLO_2") (pintype "bidirectional"))
      (node (ref "U11") (pin "3") (pinfunction "GND_3") (pintype "bidirectional"))
      (node (ref "U11") (pin "4") (pinfunction "GNDS_4") (pintype "bidirectional"))
      (node (ref "U14") (pin "2") (pinfunction "GND_2") (pintype "power_in"))
      (node (ref "U15") (pin "2") (pinfunction "GND_2") (pintype "power_in"))
      (node (ref "U16") (pin "2") (pinfunction "GND_2") (pintype "power_in"))
      (node (ref "U17") (pin "2") (pinfunction "GND_2") (pintype "power_in"))
      (node (ref "U18") (pin "1") (pinfunction "GND_1") (pintype "power_in"))
      (node (ref "U2") (pin "3") (pinfunction "GND_3") (pintype "power_in"))
      (node (ref "U2") (pin "6") (pinfunction "TABGND_6") (pintype "power_in"))
      (node (ref "U4") (pin "3") (pinfunction "GND_3") (pintype "bidirectional"))
      (node (ref "U4") (pin "4") (pinfunction "INA-_4") (pintype "bidirectional"))
      (node (ref "U5") (pin "3") (pinfunction "GND_3") (pintype "bidirectional"))
      (node (ref "U5") (pin "4") (pinfunction "INA-_4") (pintype "bidirectional"))
      (node (ref "U6") (pin "3") (pinfunction "GND_3") (pintype "bidirectional"))
      (node (ref "U6") (pin "4") (pinfunction "INA-_4") (pintype "bidirectional"))
      (node (ref "U7") (pin "3") (pinfunction "GND_3") (pintype "bidirectional"))
      (node (ref "U7") (pin "4") (pinfunction "INA-_4") (pintype "bidirectional"))
      (node (ref "U8") (pin "P$11") (pinfunction "AGND_P$11") (pintype "bidirectional"))
      (node (ref "U8") (pin "P$15") (pinfunction "AGND_P$15") (pintype "bidirectional"))
      (node (ref "U8") (pin "P$26") (pinfunction "AGND_P$26") (pintype "bidirectional"))
      (node (ref "U8") (pin "P$30") (pinfunction "AGND_P$30") (pintype "bidirectional"))
      (node (ref "U9") (pin "3") (pinfunction "GND_3") (pintype "bidirectional"))
      (node (ref "U9") (pin "4") (pinfunction "GNDS_4") (pintype "bidirectional"))
    )
    (net (code "7") (name "CAL0") (class "Default")
      (node (ref "U12") (pin "15") (pinfunction "QA_15") (pintype "tri_state"))
      (node (ref "U14") (pin "6") (pinfunction "~{A}/B_6") (pintype "input"))
    )
    (net (code "8") (name "CAL1") (class "Default")
      (node (ref "U12") (pin "1") (pinfunction "QB_1") (pintype "tri_state"))
      (node (ref "U15") (pin "6") (pinfunction "~{A}/B_6") (pintype "input"))
    )
    (net (code "9") (name "CAL2") (class "Default")
      (node (ref "U12") (pin "2") (pinfunction "QC_2") (pintype "tri_state"))
      (node (ref "U16") (pin "6") (pinfunction "~{A}/B_6") (pintype "input"))
    )
    (net (code "10") (name "CAL3") (class "Default")
      (node (ref "U12") (pin "3") (pinfunction "QD_3") (pintype "tri_state"))
      (node (ref "U17") (pin "6") (pinfunction "~{A}/B_6") (pintype "input"))
    )
    (net (code "11") (name "CS0") (class "Default")
      (node (ref "U12") (pin "4") (pinfunction "QE_4") (pintype "tri_state"))
      (node (ref "U4") (pin "10") (pinfunction "~{CS}_10") (pintype "bidirectional"))
    )
    (net (code "12") (name "CS1") (class "Default")
      (node (ref "U12") (pin "5") (pinfunction "QF_5") (pintype "tri_state"))
      (node (ref "U5") (pin "10") (pinfunction "~{CS}_10") (pintype "bidirectional"))
    )
    (net (code "13") (name "CS2") (class "Default")
      (node (ref "U12") (pin "6") (pinfunction "QG_6") (pintype "tri_state"))
      (node (ref "U6") (pin "10") (pinfunction "~{CS}_10") (pintype "bidirectional"))
    )
    (net (code "14") (name "CS3") (class "Default")
      (node (ref "U12") (pin "7") (pinfunction "QH_7") (pintype "tri_state"))
      (node (ref "U7") (pin "10") (pinfunction "~{CS}_10") (pintype "bidirectional"))
    )
    (net (code "15") (name "DGND") (class "Default")
      (node (ref "C14") (pin "2") (pinfunction "2_2") (pintype "passive"))
      (node (ref "C3") (pin "2") (pinfunction "2_2") (pintype "passive"))
      (node (ref "C31") (pin "2") (pinfunction "2_2") (pintype "passive"))
      (node (ref "C35") (pin "2") (pinfunction "2_2") (pintype "passive"))
      (node (ref "C36") (pin "2") (pinfunction "2_2") (pintype "passive"))
      (node (ref "C4") (pin "2") (pinfunction "2_2") (pintype "passive"))
      (node (ref "C7") (pin "2") (pinfunction "2_2") (pintype "passive"))
      (node (ref "C8") (pin "2") (pinfunction "2_2") (pintype "passive"))
      (node (ref "DIO") (pin "11") (pinfunction "11_11") (pintype "passive"))
      (node (ref "DIO") (pin "12") (pinfunction "12_12") (pintype "passive"))
      (node (ref "ENC-A") (pin "4") (pinfunction "S_4") (pintype "passive"))
      (node (ref "ENC-B") (pin "4") (pinfunction "S_4") (pintype "passive"))
      (node (ref "ENC_C") (pin "3") (pinfunction "3_3") (pintype "passive"))
      (node (ref "ENC_C") (pin "SH1") (pinfunction "SH1_SH1") (pintype "passive"))
      (node (ref "ENC_C") (pin "SH2") (pinfunction "SH2_SH2") (pintype "passive"))
      (node (ref "ENC_D") (pin "3") (pinfunction "3_3") (pintype "passive"))
      (node (ref "ENC_D") (pin "SH1") (pinfunction "SH1_SH1") (pintype "passive"))
      (node (ref "ENC_D") (pin "SH2") (pinfunction "SH2_SH2") (pintype "passive"))
      (node (ref "FPGA") (pin "16") (pinfunction "16_16") (pintype "passive"))
      (node (ref "L1") (pin "1") (pinfunction "1_1") (pintype "passive"))
      (node (ref "NP1") (pin "1") (pinfunction "1_1") (pintype "passive"))
      (node (ref "NP2") (pin "1") (pinfunction "1_1") (pintype "passive"))
      (node (ref "NP3") (pin "1") (pinfunction "1_1") (pintype "passive"))
      (node (ref "NP4") (pin "1") (pinfunction "1_1") (pintype "passive"))
      (node (ref "NP5") (pin "1") (pinfunction "1_1") (pintype "passive"))
      (node (ref "U1") (pin "3") (pinfunction "GND_3") (pintype "power_in"))
      (node (ref "U1") (pin "6") (pinfunction "TABGND_6") (pintype "power_in"))
      (node (ref "U12") (pin "13") (pinfunction "G_13") (pintype "input"))
      (node (ref "U12") (pin "8") (pinfunction "GND_8") (pintype "power_in"))
      (node (ref "U13") (pin "13") (pinfunction "G_13") (pintype "input"))
      (node (ref "U13") (pin "8") (pinfunction "GND_8") (pintype "power_in"))
      (node (ref "U3") (pin "3") (pinfunction "GND_3") (pintype "power_in"))
      (node (ref "U3") (pin "6") (pinfunction "TABGND_6") (pintype "power_in"))
      (node (ref "U8") (pin "P$16") (pinfunction "CLKSEL_P$16") (pintype "bidirectional"))
      (node (ref "U8") (pin "P$19") (pinfunction "DGND_P$19") (pintype "bidirectional"))
      (node (ref "XTAL") (pin "2") (pinfunction "GND_2") (pintype "power_in"))
    )
    (net (code "16") (name "DIO5") (class "Default")
      (node (ref "FPGA") (pin "5") (pinfunction "5_5") (pintype "passive"))
    )
    (net (code "17") (name "DIO6") (class "Default")
      (node (ref "DIO") (pin "8") (pinfunction "8_8") (pintype "passive"))
      (node (ref "FPGA") (pin "6") (pinfunction "6_6") (pintype "passive"))
    )
    (net (code "18") (name "DIO7") (class "Default")
      (node (ref "FPGA") (pin "7") (pinfunction "7_7") (pintype "passive"))
    )
    (net (code "19") (name "DIO8") (class "Default")
      (node (ref "DIO") (pin "7") (pinfunction "7_7") (pintype "passive"))
      (node (ref "FPGA") (pin "8") (pinfunction "8_8") (pintype "passive"))
    )
    (net (code "20") (name "DIO11") (class "Default")
      (node (ref "DIO") (pin "6") (pinfunction "6_6") (pintype "passive"))
      (node (ref "FPGA") (pin "11") (pinfunction "11_11") (pintype "passive"))
    )
    (net (code "21") (name "DIO12") (class "Default")
      (node (ref "DIO") (pin "5") (pinfunction "5_5") (pintype "passive"))
      (node (ref "FPGA") (pin "12") (pinfunction "12_12") (pintype "passive"))
    )
    (net (code "22") (name "DIO13") (class "Default")
      (node (ref "DIO") (pin "4") (pinfunction "4_4") (pintype "passive"))
      (node (ref "FPGA") (pin "13") (pinfunction "13_13") (pintype "passive"))
    )
    (net (code "23") (name "DIO14") (class "Default")
      (node (ref "DIO") (pin "3") (pinfunction "3_3") (pintype "passive"))
      (node (ref "FPGA") (pin "14") (pinfunction "14_14") (pintype "passive"))
    )
    (net (code "24") (name "DIO17") (class "Default")
      (node (ref "FPGA") (pin "17") (pinfunction "17_17") (pintype "passive"))
    )
    (net (code "25") (name "DIO18") (class "Default")
      (node (ref "FPGA") (pin "18") (pinfunction "18_18") (pintype "passive"))
    )
    (net (code "26") (name "DIO19") (class "Default")
      (node (ref "DIO") (pin "2") (pinfunction "2_2") (pintype "passive"))
      (node (ref "FPGA") (pin "19") (pinfunction "19_19") (pintype "passive"))
    )
    (net (code "27") (name "DIO20") (class "Default")
      (node (ref "DIO") (pin "1") (pinfunction "1_1") (pintype "passive"))
      (node (ref "FPGA") (pin "20") (pinfunction "20_20") (pintype "passive"))
    )
    (net (code "28") (name "DIO21") (class "Default")
      (node (ref "ENC-A") (pin "2") (pinfunction "S_2") (pintype "passive"))
      (node (ref "FPGA") (pin "21") (pinfunction "21_21") (pintype "passive"))
    )
    (net (code "29") (name "DIO22") (class "Default")
      (node (ref "ENC-A") (pin "3") (pinfunction "S_3") (pintype "passive"))
      (node (ref "FPGA") (pin "22") (pinfunction "22_22") (pintype "passive"))
    )
    (net (code "30") (name "DIO23") (class "Default")
      (node (ref "ENC-B") (pin "2") (pinfunction "S_2") (pintype "passive"))
      (node (ref "FPGA") (pin "23") (pinfunction "23_23") (pintype "passive"))
    )
    (net (code "31") (name "DIO24") (class "Default")
      (node (ref "ENC-B") (pin "3") (pinfunction "S_3") (pintype "passive"))
      (node (ref "FPGA") (pin "24") (pinfunction "24_24") (pintype "passive"))
    )
    (net (code "32") (name "DIO25") (class "Default")
      (node (ref "ENC_D") (pin "1") (pinfunction "1_1") (pintype "passive"))
      (node (ref "FPGA") (pin "25") (pinfunction "25_25") (pintype "passive"))
    )
    (net (code "33") (name "DIO26") (class "Default")
      (node (ref "ENC_D") (pin "4") (pinfunction "4_4") (pintype "passive"))
      (node (ref "FPGA") (pin "26") (pinfunction "26_26") (pintype "passive"))
    )
    (net (code "34") (name "DIO27") (class "Default")
      (node (ref "ENC_C") (pin "1") (pinfunction "1_1") (pintype "passive"))
      (node (ref "FPGA") (pin "27") (pinfunction "27_27") (pintype "passive"))
    )
    (net (code "35") (name "DIO28") (class "Default")
      (node (ref "ENC_C") (pin "4") (pinfunction "4_4") (pintype "passive"))
      (node (ref "FPGA") (pin "28") (pinfunction "28_28") (pintype "passive"))
    )
    (net (code "36") (name "DIO29") (class "Default")
      (node (ref "FPGA") (pin "29") (pinfunction "29_29") (pintype "passive"))
      (node (ref "U8") (pin "P$20") (pinfunction "CLKOUT_P$20") (pintype "bidirectional"))
    )
    (net (code "37") (name "DIO30") (class "Default")
      (node (ref "FPGA") (pin "30") (pinfunction "30_30") (pintype "passive"))
      (node (ref "U8") (pin "P$21") (pinfunction "OUTD_P$21") (pintype "bidirectional"))
    )
    (net (code "38") (name "DIO31") (class "Default")
      (node (ref "FPGA") (pin "31") (pinfunction "31_31") (pintype "passive"))
      (node (ref "U8") (pin "P$22") (pinfunction "OUTC_P$22") (pintype "bidirectional"))
    )
    (net (code "39") (name "DIO32") (class "Default")
      (node (ref "FPGA") (pin "32") (pinfunction "32_32") (pintype "passive"))
      (node (ref "U8") (pin "P$23") (pinfunction "OUTB_P$23") (pintype "bidirectional"))
    )
    (net (code "40") (name "DIO33") (class "Default")
      (node (ref "FPGA") (pin "33") (pinfunction "33_33") (pintype "passive"))
      (node (ref "U8") (pin "P$24") (pinfunction "OUTA_P$24") (pintype "bidirectional"))
    )
    (net (code "41") (name "DIO34") (class "Default")
      (node (ref "FPGA") (pin "34") (pinfunction "34_34") (pintype "passive"))
      (node (ref "U10") (pin "8") (pinfunction "SCK_8") (pintype "bidirectional"))
      (node (ref "U12") (pin "11") (pinfunction "SCK_11") (pintype "input"))
      (node (ref "U13") (pin "11") (pinfunction "SCK_11") (pintype "input"))
    )
    (net (code "42") (name "DIO35") (class "Default")
      (node (ref "FPGA") (pin "35") (pinfunction "35_35") (pintype "passive"))
      (node (ref "U10") (pin "7") (pinfunction "~{CS}/LD_7") (pintype "bidirectional"))
    )
    (net (code "43") (name "DIO36") (class "Default")
      (node (ref "FPGA") (pin "36") (pinfunction "36_36") (pintype "passive"))
      (node (ref "U10") (pin "9") (pinfunction "SDI_9") (pintype "bidirectional"))
      (node (ref "U12") (pin "14") (pinfunction "SER_14") (pintype "input"))
    )
    (net (code "44") (name "DIO37") (class "Default")
      (node (ref "FPGA") (pin "37") (pinfunction "37_37") (pintype "passive"))
      (node (ref "U12") (pin "10") (pinfunction "SCL_10") (pintype "input"))
      (node (ref "U13") (pin "10") (pinfunction "SCL_10") (pintype "input"))
    )
    (net (code "45") (name "DIO38") (class "Default")
      (node (ref "FPGA") (pin "38") (pinfunction "38_38") (pintype "passive"))
      (node (ref "U12") (pin "12") (pinfunction "RCK_12") (pintype "input"))
      (node (ref "U13") (pin "12") (pinfunction "RCK_12") (pintype "input"))
    )
    (net (code "46") (name "DIO39") (class "Default")
      (node (ref "FPGA") (pin "39") (pinfunction "39_39") (pintype "passive"))
      (node (ref "U4") (pin "2") (pinfunction "DIN_2") (pintype "bidirectional"))
      (node (ref "U5") (pin "2") (pinfunction "DIN_2") (pintype "bidirectional"))
      (node (ref "U6") (pin "2") (pinfunction "DIN_2") (pintype "bidirectional"))
      (node (ref "U7") (pin "2") (pinfunction "DIN_2") (pintype "bidirectional"))
    )
    (net (code "47") (name "DIO40") (class "Default")
      (node (ref "FPGA") (pin "40") (pinfunction "40_40") (pintype "passive"))
      (node (ref "U4") (pin "1") (pinfunction "SCK_1") (pintype "bidirectional"))
      (node (ref "U5") (pin "1") (pinfunction "SCK_1") (pintype "bidirectional"))
      (node (ref "U6") (pin "1") (pinfunction "SCK_1") (pintype "bidirectional"))
      (node (ref "U7") (pin "1") (pinfunction "SCK_1") (pintype "bidirectional"))
    )
    (net (code "48") (name "GPIO0") (class "Default")
      (node (ref "U13") (pin "4") (pinfunction "QE_4") (pintype "tri_state"))
    )
    (net (code "49") (name "GPIO1") (class "Default")
      (node (ref "U13") (pin "5") (pinfunction "QF_5") (pintype "tri_state"))
    )
    (net (code "50") (name "GPIO2") (class "Default")
      (node (ref "U13") (pin "6") (pinfunction "QG_6") (pintype "tri_state"))
    )
    (net (code "51") (name "GPIO3") (class "Default")
      (node (ref "U13") (pin "7") (pinfunction "QH_7") (pintype "tri_state"))
    )
    (net (code "52") (name "LED0") (class "Default")
      (node (ref "LED1") (pin "AR1") (pinfunction "AR1_AR1") (pintype "passive"))
      (node (ref "U13") (pin "15") (pinfunction "QA_15") (pintype "tri_state"))
    )
    (net (code "53") (name "LED1") (class "Default")
      (node (ref "R6") (pin "2") (pinfunction "2_2") (pintype "passive"))
      (node (ref "U13") (pin "1") (pinfunction "QB_1") (pintype "tri_state"))
    )
    (net (code "54") (name "LED2") (class "Default")
      (node (ref "LED1") (pin "AR2") (pinfunction "AR2_AR2") (pintype "passive"))
      (node (ref "U13") (pin "2") (pinfunction "QC_2") (pintype "tri_state"))
    )
    (net (code "55") (name "LED3") (class "Default")
      (node (ref "R7") (pin "2") (pinfunction "2_2") (pintype "passive"))
      (node (ref "U13") (pin "3") (pinfunction "QD_3") (pintype "tri_state"))
    )
    (net (code "56") (name "MCLK") (class "Default")
      (node (ref "U8") (pin "P$17") (pinfunction "CLKIN_P$17") (pintype "bidirectional"))
      (node (ref "XTAL") (pin "3") (pinfunction "OUT_3") (pintype "output"))
    )
    (net (code "57") (name "Net-(LED1-PadAG1)") (class "Default")
      (node (ref "LED1") (pin "AG1") (pinfunction "AG1_AG1") (pintype "passive"))
      (node (ref "R6") (pin "1") (pinfunction "1_1") (pintype "passive"))
    )
    (net (code "58") (name "Net-(LED1-PadAG2)") (class "Default")
      (node (ref "LED1") (pin "AG2") (pinfunction "AG2_AG2") (pintype "passive"))
      (node (ref "R7") (pin "1") (pinfunction "1_1") (pintype "passive"))
    )
    (net (code "59") (name "Net-(NP6-Pad2)") (class "Default")
      (node (ref "NP6") (pin "2") (pinfunction "2_2") (pintype "passive"))
      (node (ref "NP7") (pin "1") (pinfunction "1_1") (pintype "passive"))
    )
    (net (code "60") (name "Net-(NP8-Pad2)") (class "Default")
      (node (ref "NP8") (pin "2") (pinfunction "2_2") (pintype "passive"))
      (node (ref "NP9") (pin "2") (pinfunction "2_2") (pintype "passive"))
    )
    (net (code "61") (name "Net-(PSWA-S)") (class "Default")
      (node (ref "J1") (pin "3") (pinfunction "3_3") (pintype "passive"))
      (node (ref "PSW") (pin "1") (pinfunction "S_1") (pintype "passive"))
    )
    (net (code "62") (name "Net-(PSWB-S)") (class "Default")
      (node (ref "C1") (pin "+") (pinfunction "+_+") (pintype "passive"))
      (node (ref "C2") (pin "1") (pinfunction "1_1") (pintype "passive"))
      (node (ref "C3") (pin "1") (pinfunction "1_1") (pintype "passive"))
      (node (ref "C7") (pin "1") (pinfunction "1_1") (pintype "passive"))
      (node (ref "L2") (pin "2") (pinfunction "2_2") (pintype "passive"))
      (node (ref "L3") (pin "2") (pinfunction "2_2") (pintype "passive"))
      (node (ref "NP7") (pin "2") (pinfunction "2_2") (pintype "passive"))
      (node (ref "PSW") (pin "2") (pinfunction "S_2") (pintype "passive"))
      (node (ref "R4") (pin "2") (pinfunction "2_2") (pintype "passive"))
      (node (ref "R5") (pin "2") (pinfunction "2_2") (pintype "passive"))
      (node (ref "U1") (pin "2") (pinfunction "VIN_2") (pintype "input"))
      (node (ref "U3") (pin "2") (pinfunction "VIN_2") (pintype "input"))
    )
    (net (code "63") (name "Net-(U1-~{SD})") (class "Default")
      (node (ref "R5") (pin "1") (pinfunction "1_1") (pintype "passive"))
      (node (ref "U1") (pin "1") (pinfunction "~{SD}_1") (pintype "input"))
    )
    (net (code "64") (name "Net-(U2-VIN)") (class "Default")
      (node (ref "C5") (pin "1") (pinfunction "1_1") (pintype "passive"))
      (node (ref "L2") (pin "1") (pinfunction "1_1") (pintype "passive"))
      (node (ref "R3") (pin "2") (pinfunction "2_2") (pintype "passive"))
      (node (ref "U2") (pin "2") (pinfunction "VIN_2") (pintype "input"))
    )
    (net (code "65") (name "Net-(U2-~{SD})") (class "Default")
      (node (ref "R3") (pin "1") (pinfunction "1_1") (pintype "passive"))
      (node (ref "U2") (pin "1") (pinfunction "~{SD}_1") (pintype "input"))
    )
    (net (code "66") (name "Net-(U3-~{SD})") (class "Default")
      (node (ref "R4") (pin "1") (pinfunction "1_1") (pintype "passive"))
      (node (ref "U3") (pin "1") (pinfunction "~{SD}_1") (pintype "input"))
    )
    (net (code "67") (name "Net-(U4-INB)") (class "Default")
      (node (ref "U4") (pin "6") (pinfunction "OUTB_6") (pintype "bidirectional"))
      (node (ref "U4") (pin "7") (pinfunction "INB_7") (pintype "bidirectional"))
    )
    (net (code "68") (name "Net-(U4-OUTA)") (class "Default")
      (node (ref "R18") (pin "1") (pinfunction "1_1") (pintype "passive"))
      (node (ref "U4") (pin "8") (pinfunction "OUTA_8") (pintype "bidirectional"))
    )
    (net (code "69") (name "Net-(U5-INB)") (class "Default")
      (node (ref "U5") (pin "6") (pinfunction "OUTB_6") (pintype "bidirectional"))
      (node (ref "U5") (pin "7") (pinfunction "INB_7") (pintype "bidirectional"))
    )
    (net (code "70") (name "Net-(U5-OUTA)") (class "Default")
      (node (ref "R19") (pin "1") (pinfunction "1_1") (pintype "passive"))
      (node (ref "U5") (pin "8") (pinfunction "OUTA_8") (pintype "bidirectional"))
    )
    (net (code "71") (name "Net-(U6-INB)") (class "Default")
      (node (ref "U6") (pin "6") (pinfunction "OUTB_6") (pintype "bidirectional"))
      (node (ref "U6") (pin "7") (pinfunction "INB_7") (pintype "bidirectional"))
    )
    (net (code "72") (name "Net-(U6-OUTA)") (class "Default")
      (node (ref "R20") (pin "1") (pinfunction "1_1") (pintype "passive"))
      (node (ref "U6") (pin "8") (pinfunction "OUTA_8") (pintype "bidirectional"))
    )
    (net (code "73") (name "Net-(U7-INB)") (class "Default")
      (node (ref "U7") (pin "6") (pinfunction "OUTB_6") (pintype "bidirectional"))
      (node (ref "U7") (pin "7") (pinfunction "INB_7") (pintype "bidirectional"))
    )
    (net (code "74") (name "Net-(U7-OUTA)") (class "Default")
      (node (ref "R21") (pin "1") (pinfunction "1_1") (pintype "passive"))
      (node (ref "U7") (pin "8") (pinfunction "OUTA_8") (pintype "bidirectional"))
    )
    (net (code "75") (name "Net-(U8-CHA+)") (class "Default")
      (node (ref "C10") (pin "1") (pinfunction "1_1") (pintype "passive"))
      (node (ref "R18") (pin "2") (pinfunction "2_2") (pintype "passive"))
      (node (ref "U8") (pin "P$1") (pinfunction "CHA+_P$1") (pintype "bidirectional"))
    )
    (net (code "76") (name "Net-(U8-CHA-)") (class "Default")
      (node (ref "U8") (pin "P$10") (pinfunction "REFC_P$10") (pintype "bidirectional"))
      (node (ref "U8") (pin "P$2") (pinfunction "CHA-_P$2") (pintype "bidirectional"))
      (node (ref "U8") (pin "P$28") (pinfunction "REFOUT_P$28") (pintype "bidirectional"))
      (node (ref "U8") (pin "P$31") (pinfunction "REFB_P$31") (pintype "bidirectional"))
      (node (ref "U8") (pin "P$32") (pinfunction "REFA_P$32") (pintype "bidirectional"))
      (node (ref "U8") (pin "P$4") (pinfunction "CHB-_P$4") (pintype "bidirectional"))
      (node (ref "U8") (pin "P$5") (pinfunction "CHC-_P$5") (pintype "bidirectional"))
      (node (ref "U8") (pin "P$7") (pinfunction "CHD-_P$7") (pintype "bidirectional"))
      (node (ref "U8") (pin "P$9") (pinfunction "REFD_P$9") (pintype "bidirectional"))
    )
    (net (code "77") (name "Net-(U8-CHB+)") (class "Default")
      (node (ref "C11") (pin "1") (pinfunction "1_1") (pintype "passive"))
      (node (ref "R19") (pin "2") (pinfunction "2_2") (pintype "passive"))
      (node (ref "U8") (pin "P$3") (pinfunction "CHB+_P$3") (pintype "bidirectional"))
    )
    (net (code "78") (name "Net-(U8-CHC+)") (class "Default")
      (node (ref "C12") (pin "1") (pinfunction "1_1") (pintype "passive"))
      (node (ref "R20") (pin "2") (pinfunction "2_2") (pintype "passive"))
      (node (ref "U8") (pin "P$6") (pinfunction "CHC+_P$6") (pintype "bidirectional"))
    )
    (net (code "79") (name "Net-(U8-CHD+)") (class "Default")
      (node (ref "C13") (pin "1") (pinfunction "1_1") (pintype "passive"))
      (node (ref "R21") (pin "2") (pinfunction "2_2") (pintype "passive"))
      (node (ref "U8") (pin "P$8") (pinfunction "CHD+_P$8") (pintype "bidirectional"))
    )
    (net (code "80") (name "Net-(U9-NR)") (class "Default")
      (node (ref "C20") (pin "1") (pinfunction "1_1") (pintype "passive"))
      (node (ref "U9") (pin "1") (pinfunction "NR_1") (pintype "bidirectional"))
    )
    (net (code "81") (name "Net-(U10-REFA)") (class "Default")
      (node (ref "C21") (pin "1") (pinfunction "1_1") (pintype "passive"))
      (node (ref "U10") (pin "12") (pinfunction "REFC_12") (pintype "bidirectional"))
      (node (ref "U10") (pin "15") (pinfunction "REFD_15") (pintype "bidirectional"))
      (node (ref "U10") (pin "3") (pinfunction "REFA_3") (pintype "bidirectional"))
      (node (ref "U10") (pin "6") (pinfunction "REFB_6") (pintype "bidirectional"))
      (node (ref "U9") (pin "6") (pinfunction "OUTS_6") (pintype "bidirectional"))
      (node (ref "U9") (pin "7") (pinfunction "OUTF_7") (pintype "bidirectional"))
    )
    (net (code "82") (name "Net-(U10-VOUTA)") (class "Default")
      (node (ref "U10") (pin "4") (pinfunction "VOUTA_4") (pintype "bidirectional"))
      (node (ref "U20") (pin "3") (pinfunction "+IN_3") (pintype "input"))
    )
    (net (code "83") (name "Net-(U10-VOUTB)") (class "Default")
      (node (ref "U10") (pin "5") (pinfunction "VOUTB_5") (pintype "bidirectional"))
      (node (ref "U21") (pin "3") (pinfunction "+IN_3") (pintype "input"))
    )
    (net (code "84") (name "Net-(U10-VOUTC)") (class "Default")
      (node (ref "U10") (pin "13") (pinfunction "VOUTC_13") (pintype "bidirectional"))
      (node (ref "U22") (pin "3") (pinfunction "+IN_3") (pintype "input"))
    )
    (net (code "85") (name "Net-(U10-VOUTD)") (class "Default")
      (node (ref "U10") (pin "14") (pinfunction "VOUTD_14") (pintype "bidirectional"))
      (node (ref "U23") (pin "3") (pinfunction "+IN_3") (pintype "input"))
    )
    (net (code "86") (name "Net-(U11-NR)") (class "Default")
      (node (ref "C33") (pin "1") (pinfunction "1_1") (pintype "passive"))
      (node (ref "U11") (pin "1") (pinfunction "NR_1") (pintype "bidirectional"))
    )
    (net (code "87") (name "Net-(U11-OUTF)") (class "Default")
      (node (ref "C32") (pin "1") (pinfunction "1_1") (pintype "passive"))
      (node (ref "U11") (pin "6") (pinfunction "OUTS_6") (pintype "bidirectional"))
      (node (ref "U11") (pin "7") (pinfunction "OUTF_7") (pintype "bidirectional"))
      (node (ref "U14") (pin "1") (pinfunction "B_1") (pintype "bidirectional"))
      (node (ref "U15") (pin "1") (pinfunction "B_1") (pintype "bidirectional"))
      (node (ref "U16") (pin "1") (pinfunction "B_1") (pintype "bidirectional"))
      (node (ref "U17") (pin "1") (pinfunction "B_1") (pintype "bidirectional"))
    )
    (net (code "88") (name "Net-(U12A-QH*)") (class "Default")
      (node (ref "U12") (pin "9") (pinfunction "QH*_9") (pintype "tri_state"))
      (node (ref "U13") (pin "14") (pinfunction "SER_14") (pintype "input"))
    )
    (net (code "89") (name "Net-(U14A-A)") (class "Default")
      (node (ref "INA") (pin "2") (pinfunction "2_2") (pintype "passive"))
      (node (ref "U14") (pin "3") (pinfunction "A_3") (pintype "bidirectional"))
    )
    (net (code "90") (name "Net-(U14A-X)") (class "Default")
      (node (ref "U14") (pin "4") (pinfunction "X_4") (pintype "bidirectional"))
      (node (ref "U4") (pin "5") (pinfunction "INA+_5") (pintype "bidirectional"))
    )
    (net (code "91") (name "Net-(U15A-A)") (class "Default")
      (node (ref "INB") (pin "2") (pinfunction "2_2") (pintype "passive"))
      (node (ref "U15") (pin "3") (pinfunction "A_3") (pintype "bidirectional"))
    )
    (net (code "92") (name "Net-(U15A-X)") (class "Default")
      (node (ref "U15") (pin "4") (pinfunction "X_4") (pintype "bidirectional"))
      (node (ref "U5") (pin "5") (pinfunction "INA+_5") (pintype "bidirectional"))
    )
    (net (code "93") (name "Net-(U16A-A)") (class "Default")
      (node (ref "INC") (pin "2") (pinfunction "2_2") (pintype "passive"))
      (node (ref "U16") (pin "3") (pinfunction "A_3") (pintype "bidirectional"))
    )
    (net (code "94") (name "Net-(U16A-X)") (class "Default")
      (node (ref "U16") (pin "4") (pinfunction "X_4") (pintype "bidirectional"))
      (node (ref "U6") (pin "5") (pinfunction "INA+_5") (pintype "bidirectional"))
    )
    (net (code "95") (name "Net-(U17A-A)") (class "Default")
      (node (ref "IND") (pin "2") (pinfunction "2_2") (pintype "passive"))
      (node (ref "U17") (pin "3") (pinfunction "A_3") (pintype "bidirectional"))
    )
    (net (code "96") (name "Net-(U17A-X)") (class "Default")
      (node (ref "U17") (pin "4") (pinfunction "X_4") (pintype "bidirectional"))
      (node (ref "U7") (pin "5") (pinfunction "INA+_5") (pintype "bidirectional"))
    )
    (net (code "97") (name "Net-(U18-BYP)") (class "Default")
      (node (ref "C39") (pin "1") (pinfunction "1_1") (pintype "passive"))
      (node (ref "U18") (pin "3") (pinfunction "BYP_3") (pintype "bidirectional"))
    )
    (net (code "98") (name "Net-(U18-IN)") (class "Default")
      (node (ref "C1") (pin "-") (pinfunction "-_-") (pintype "passive"))
      (node (ref "C2") (pin "2") (pinfunction "2_2") (pintype "passive"))
      (node (ref "C40") (pin "1") (pinfunction "1_1") (pintype "passive"))
      (node (ref "J1") (pin "1") (pinfunction "1_1") (pintype "passive"))
      (node (ref "NP9") (pin "1") (pinfunction "1_1") (pintype "passive"))
      (node (ref "U18") (pin "2") (pinfunction "IN_2") (pintype "bidirectional"))
      (node (ref "U18") (pin "4") (pinfunction "~{SHDN}_4") (pintype "bidirectional"))
    )
    (net (code "99") (name "Net-(U19-+IN)") (class "Default")
      (node (ref "R8") (pin "1") (pinfunction "1_1") (pintype "passive"))
      (node (ref "R9") (pin "2") (pinfunction "2_2") (pintype "passive"))
      (node (ref "U19") (pin "3") (pinfunction "+IN_3") (pintype "input"))
    )
    (net (code "100") (name "Net-(U19--IN)") (class "Default")
      (node (ref "U19") (pin "1") (pinfunction "OUT_1") (pintype "output"))
      (node (ref "U19") (pin "4") (pinfunction "-IN_4") (pintype "input"))
      (node (ref "U20") (pin "5") (pinfunction "+IN_5") (pintype "input"))
      (node (ref "U21") (pin "5") (pinfunction "+IN_5") (pintype "input"))
      (node (ref "U22") (pin "5") (pinfunction "+IN_5") (pintype "input"))
      (node (ref "U23") (pin "5") (pinfunction "+IN_5") (pintype "input"))
    )
    (net (code "101") (name "Net-(U20A--IN)") (class "Default")
      (node (ref "R10") (pin "1") (pinfunction "1_1") (pintype "passive"))
      (node (ref "U20") (pin "1") (pinfunction "OUT_1") (pintype "output"))
      (node (ref "U20") (pin "2") (pinfunction "-IN_2") (pintype "input"))
    )
    (net (code "102") (name "Net-(U20B--IN)") (class "Default")
      (node (ref "R10") (pin "2") (pinfunction "2_2") (pintype "passive"))
      (node (ref "R11") (pin "1") (pinfunction "1_1") (pintype "passive"))
      (node (ref "U20") (pin "6") (pinfunction "-IN_6") (pintype "input"))
    )
    (net (code "103") (name "Net-(U20B-OUT)") (class "Default")
      (node (ref "OUTAB") (pin "3") (pinfunction "3_3") (pintype "passive"))
      (node (ref "R11") (pin "2") (pinfunction "2_2") (pintype "passive"))
      (node (ref "U20") (pin "7") (pinfunction "OUT_7") (pintype "output"))
    )
    (net (code "104") (name "Net-(U21A--IN)") (class "Default")
      (node (ref "R12") (pin "1") (pinfunction "1_1") (pintype "passive"))
      (node (ref "U21") (pin "1") (pinfunction "OUT_1") (pintype "output"))
      (node (ref "U21") (pin "2") (pinfunction "-IN_2") (pintype "input"))
    )
    (net (code "105") (name "Net-(U21B--IN)") (class "Default")
      (node (ref "R12") (pin "2") (pinfunction "2_2") (pintype "passive"))
      (node (ref "R13") (pin "1") (pinfunction "1_1") (pintype "passive"))
      (node (ref "U21") (pin "6") (pinfunction "-IN_6") (pintype "input"))
    )
    (net (code "106") (name "Net-(U21B-OUT)") (class "Default")
      (node (ref "OUTAB") (pin "2") (pinfunction "2_2") (pintype "passive"))
      (node (ref "R13") (pin "2") (pinfunction "2_2") (pintype "passive"))
      (node (ref "U21") (pin "7") (pinfunction "OUT_7") (pintype "output"))
    )
    (net (code "107") (name "Net-(U22A--IN)") (class "Default")
      (node (ref "R14") (pin "1") (pinfunction "1_1") (pintype "passive"))
      (node (ref "U22") (pin "1") (pinfunction "OUT_1") (pintype "output"))
      (node (ref "U22") (pin "2") (pinfunction "-IN_2") (pintype "input"))
    )
    (net (code "108") (name "Net-(U22B--IN)") (class "Default")
      (node (ref "R14") (pin "2") (pinfunction "2_2") (pintype "passive"))
      (node (ref "R15") (pin "1") (pinfunction "1_1") (pintype "passive"))
      (node (ref "U22") (pin "6") (pinfunction "-IN_6") (pintype "input"))
    )
    (net (code "109") (name "Net-(U22B-OUT)") (class "Default")
      (node (ref "OUTCD") (pin "3") (pinfunction "3_3") (pintype "passive"))
      (node (ref "R15") (pin "2") (pinfunction "2_2") (pintype "passive"))
      (node (ref "U22") (pin "7") (pinfunction "OUT_7") (pintype "output"))
    )
    (net (code "110") (name "Net-(U23A--IN)") (class "Default")
      (node (ref "R16") (pin "1") (pinfunction "1_1") (pintype "passive"))
      (node (ref "U23") (pin "1") (pinfunction "OUT_1") (pintype "output"))
      (node (ref "U23") (pin "2") (pinfunction "-IN_2") (pintype "input"))
    )
    (net (code "111") (name "Net-(U23B--IN)") (class "Default")
      (node (ref "R16") (pin "2") (pinfunction "2_2") (pintype "passive"))
      (node (ref "R17") (pin "1") (pinfunction "1_1") (pintype "passive"))
      (node (ref "U23") (pin "6") (pinfunction "-IN_6") (pintype "input"))
    )
    (net (code "112") (name "Net-(U23B-OUT)") (class "Default")
      (node (ref "OUTCD") (pin "2") (pinfunction "2_2") (pintype "passive"))
      (node (ref "R17") (pin "2") (pinfunction "2_2") (pintype "passive"))
      (node (ref "U23") (pin "7") (pinfunction "OUT_7") (pintype "output"))
    )
    (net (code "113") (name "RST") (class "Default")
      (node (ref "FPGA") (pin "9") (pinfunction "9_9") (pintype "passive"))
    )
    (net (code "114") (name "unconnected-(ENC_C-Pad2)") (class "Default")
      (node (ref "ENC_C") (pin "2") (pinfunction "2_2") (pintype "passive"))
    )
    (net (code "115") (name "unconnected-(ENC_D-Pad2)") (class "Default")
      (node (ref "ENC_D") (pin "2") (pinfunction "2_2") (pintype "passive"))
    )
    (net (code "116") (name "unconnected-(FPGA-Pad1)") (class "Default")
      (node (ref "FPGA") (pin "1") (pinfunction "1_1") (pintype "passive"))
    )
    (net (code "117") (name "unconnected-(FPGA-Pad2)") (class "Default")
      (node (ref "FPGA") (pin "2") (pinfunction "2_2") (pintype "passive"))
    )
    (net (code "118") (name "unconnected-(FPGA-Pad3)") (class "Default")
      (node (ref "FPGA") (pin "3") (pinfunction "3_3") (pintype "passive"))
    )
    (net (code "119") (name "unconnected-(FPGA-Pad4)") (class "Default")
      (node (ref "FPGA") (pin "4") (pinfunction "4_4") (pintype "passive"))
    )
    (net (code "120") (name "unconnected-(FPGA-Pad10)") (class "Default")
      (node (ref "FPGA") (pin "10") (pinfunction "10_10") (pintype "passive"))
    )
    (net (code "121") (name "unconnected-(FPGA-Pad41)") (class "Default")
      (node (ref "FPGA") (pin "41") (pinfunction "41_41") (pintype "passive"))
    )
    (net (code "122") (name "unconnected-(FPGA-Pad42)") (class "Default")
      (node (ref "FPGA") (pin "42") (pinfunction "42_42") (pintype "passive"))
    )
    (net (code "123") (name "unconnected-(FPGA-Pad43)") (class "Default")
      (node (ref "FPGA") (pin "43") (pinfunction "43_43") (pintype "passive"))
    )
    (net (code "124") (name "unconnected-(FPGA-Pad44)") (class "Default")
      (node (ref "FPGA") (pin "44") (pinfunction "44_44") (pintype "passive"))
    )
    (net (code "125") (name "unconnected-(J1-Pad2)") (class "Default")
      (node (ref "J1") (pin "2") (pinfunction "2_2") (pintype "passive"))
    )
    (net (code "126") (name "unconnected-(U10-SDO-Pad10)") (class "Default")
      (node (ref "U10") (pin "10") (pinfunction "SDO_10") (pintype "bidirectional"))
    )
    (net (code "127") (name "unconnected-(U13A-QH*-Pad9)") (class "Default")
      (node (ref "U13") (pin "9") (pinfunction "QH*_9") (pintype "tri_state"))
    )
    (net (code "128") (name "unconnected-(XTAL-TRI-Pad1)") (class "Default")
      (node (ref "XTAL") (pin "1") (pinfunction "TRI_1") (pintype "input"))
    )
  )
)
